# FPGA.net
KiCad netlist of a schematic drawn in Altium Designer
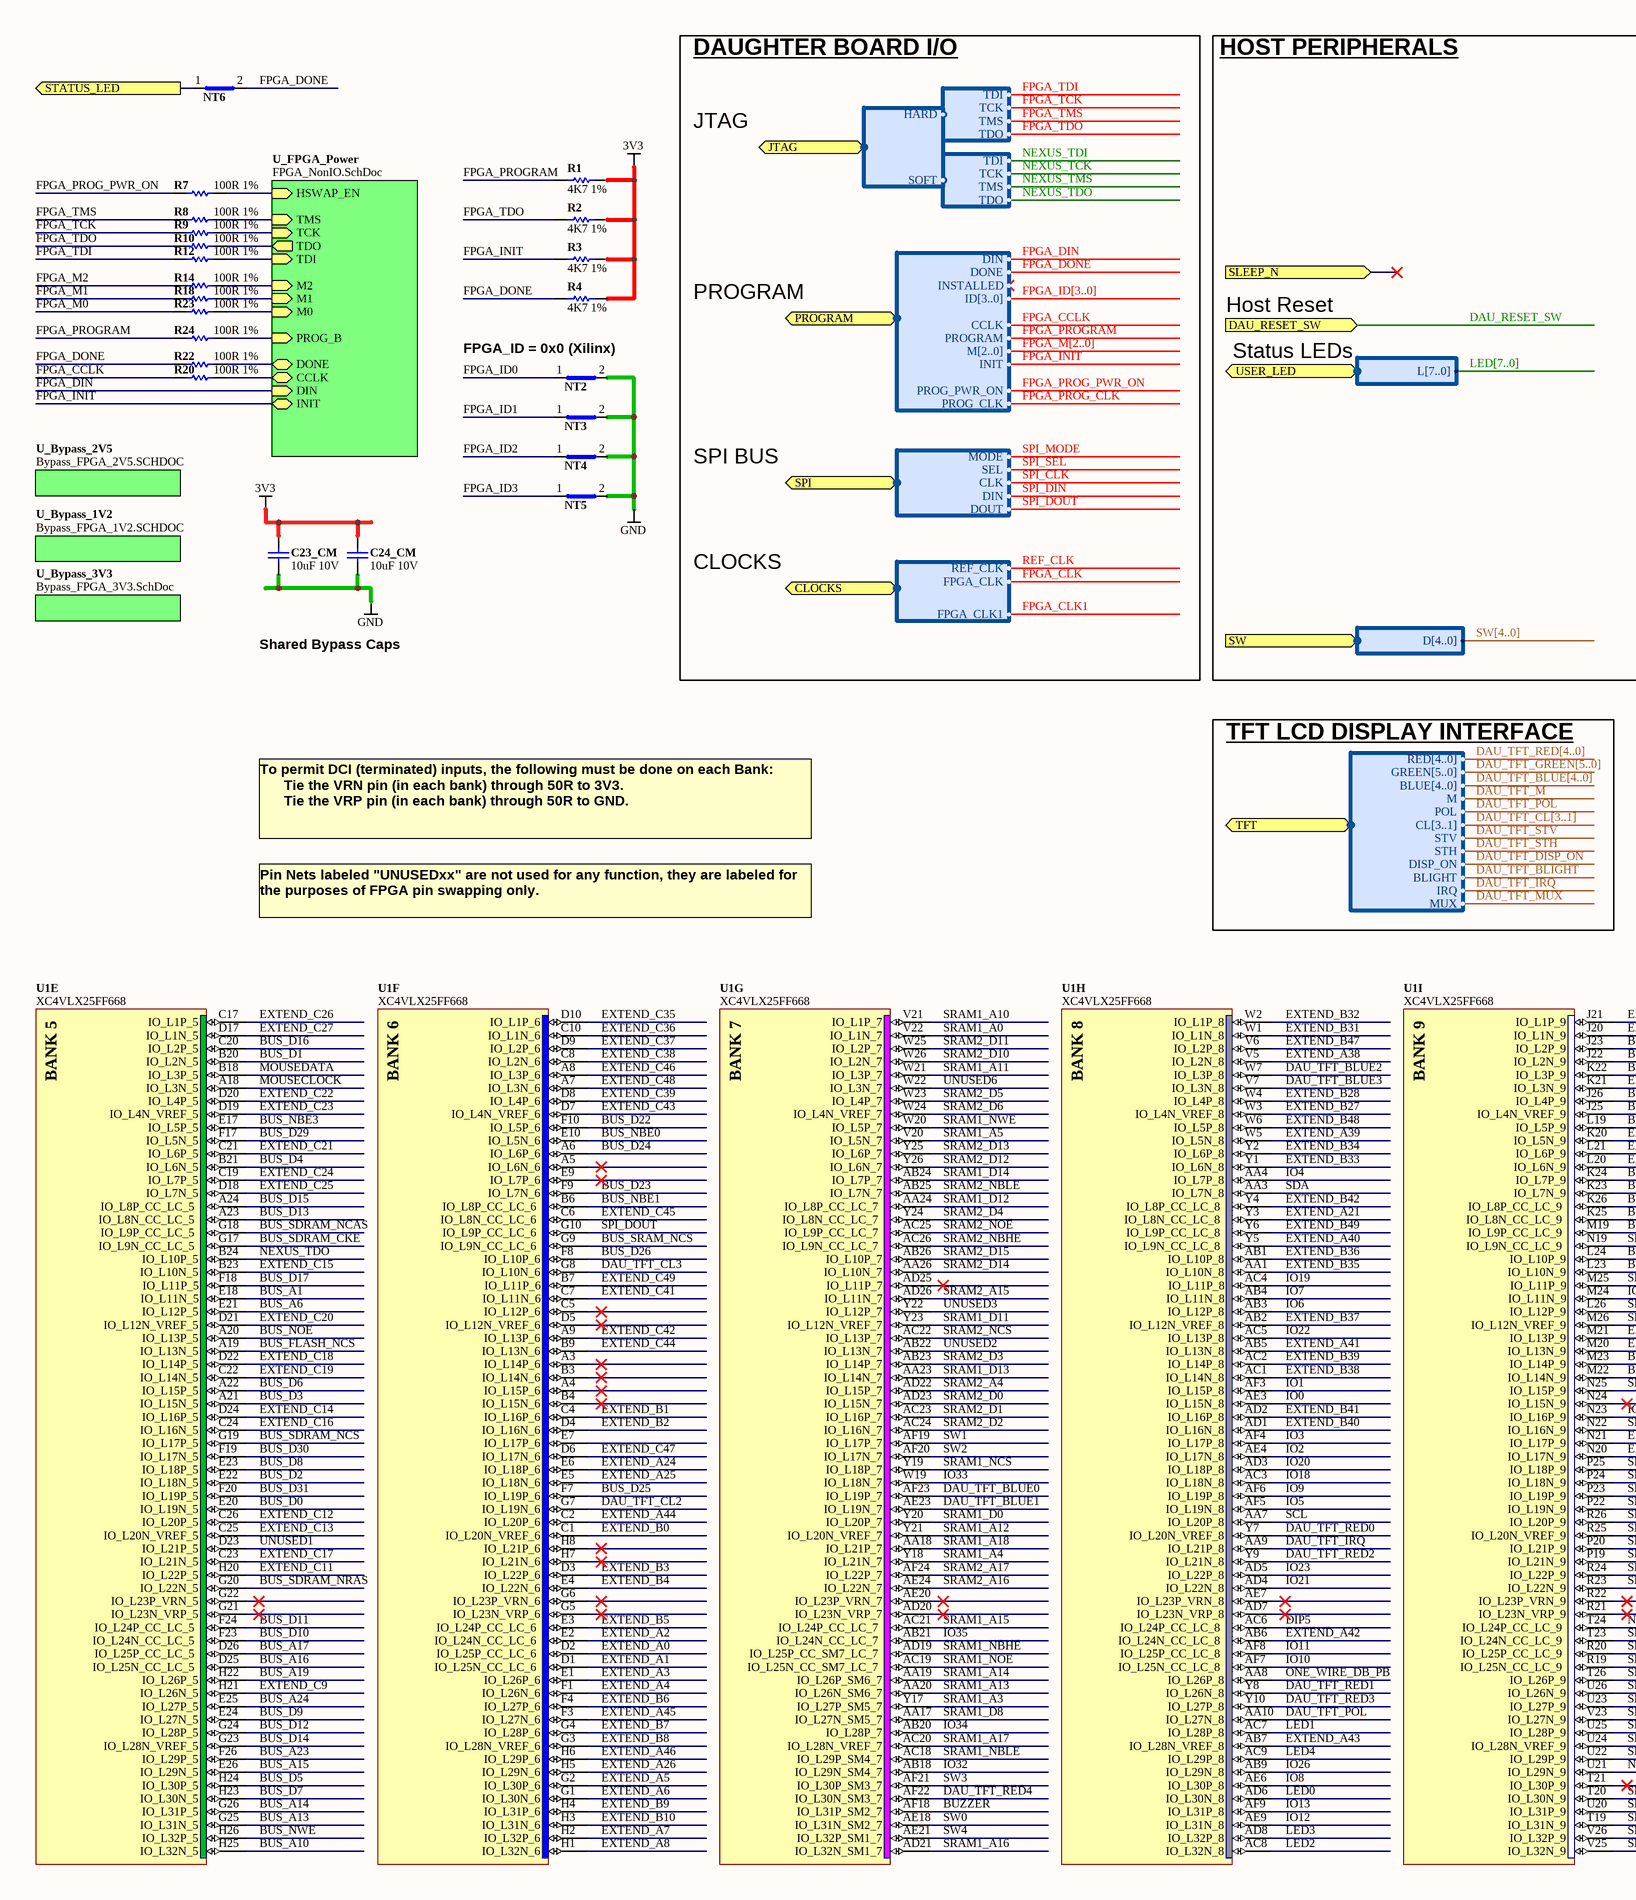
[diagram p0: FPGA.SCHDOC, left]
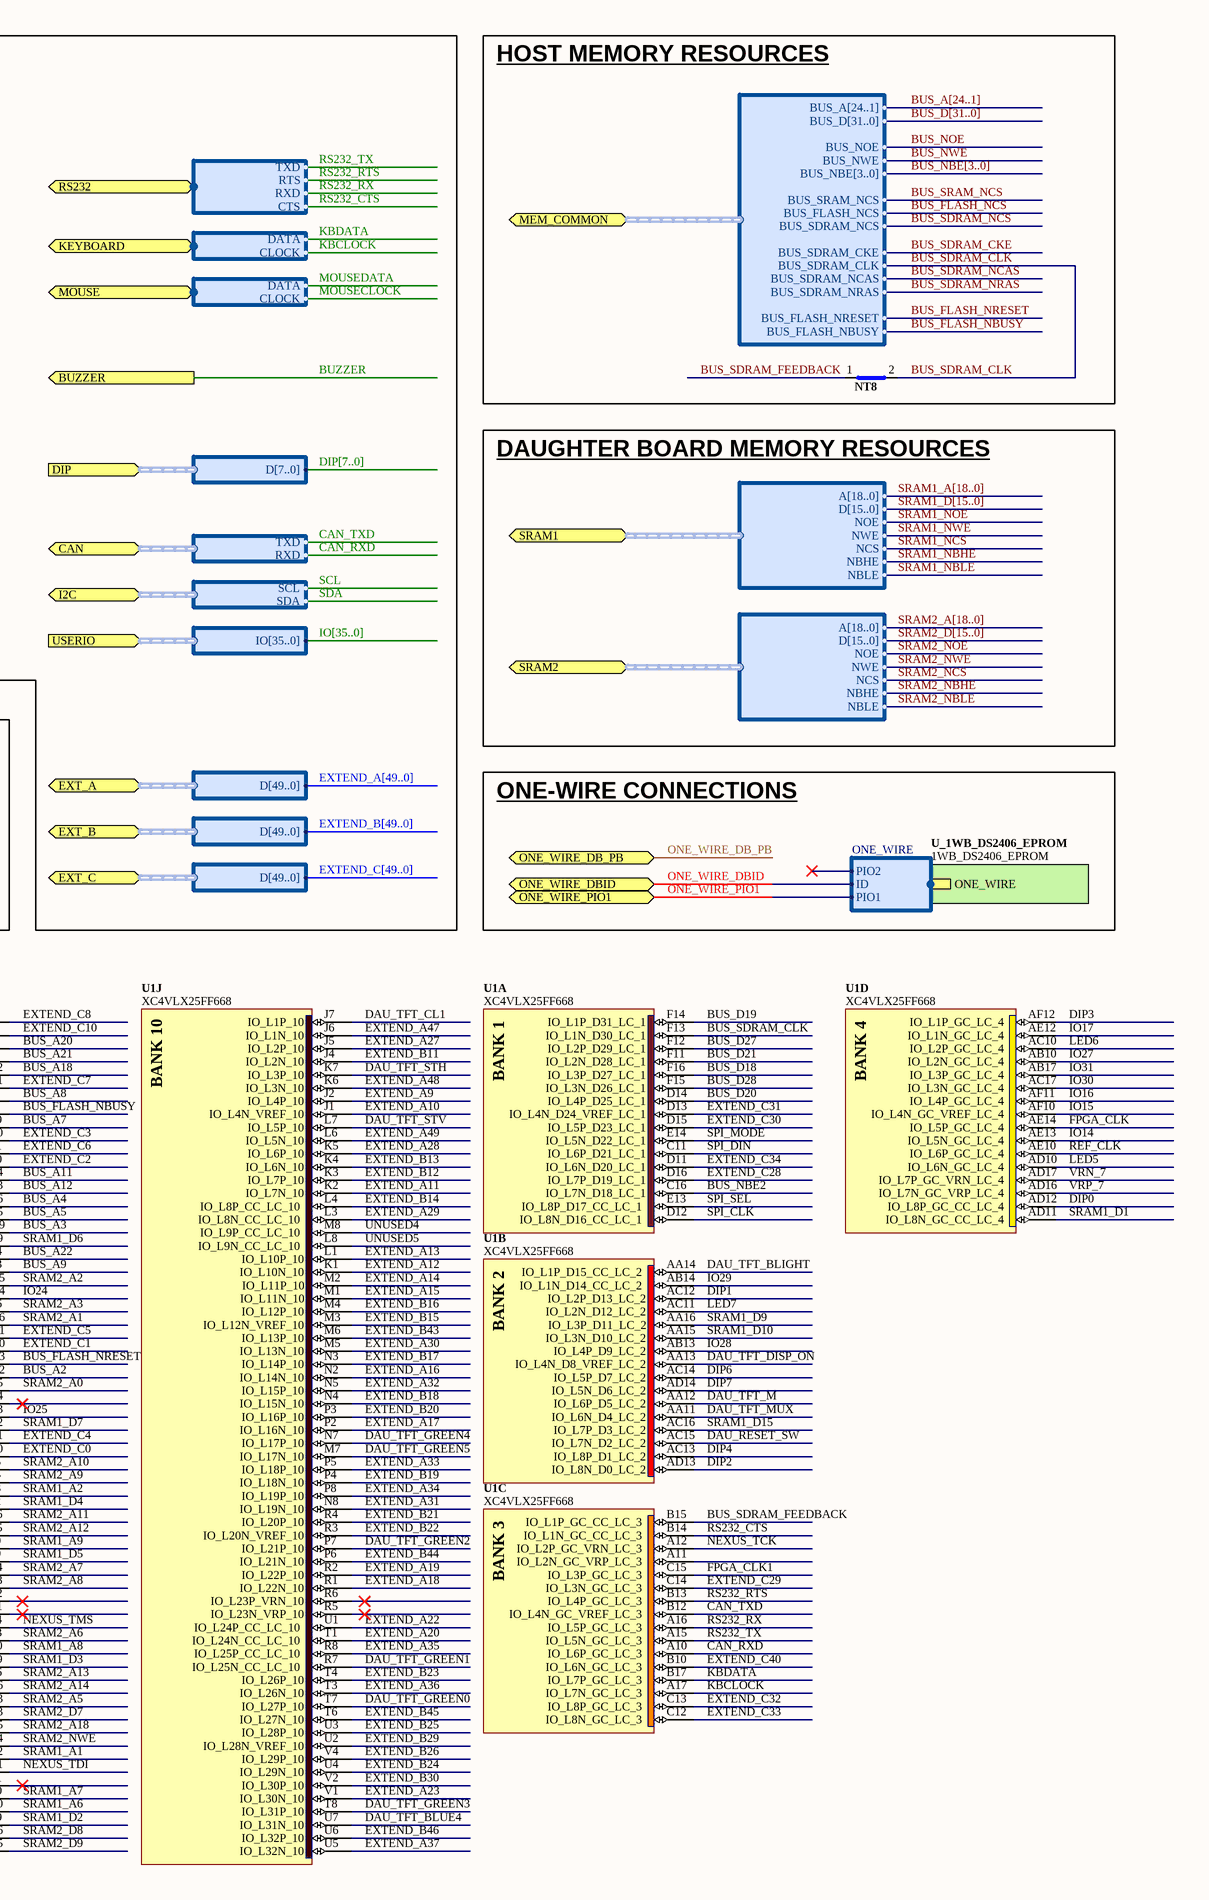
[diagram p1: FPGA.SCHDOC, right]

(export (version "E")
  (design (tool "Eeschema 10.0.6"))
  (components
    (comp (ref "C23_CM")
      (value "10uF 10V")
      (footprint "CAPC2012-STAR")
      (description "Capacitor, Ceramic, 10uF 10% 10V 0805 (2012) X5R")
      (fields (field (name "TOLERANCE") "10 %"))
      (libsource (lib "AltiumDesignLibrary") (part "CAP-NP"))
    )
    (comp (ref "C24_CM")
      (value "10uF 10V")
      (footprint "CAPC2012-STAR")
      (description "Capacitor, Ceramic, 10uF 10% 10V 0805 (2012) X5R")
      (fields (field (name "TOLERANCE") "10 %"))
      (libsource (lib "AltiumDesignLibrary") (part "CAP-NP"))
    )
    (comp (ref "NT2")
      (value "Net Tie SMT2")
      (footprint "NETTIE-SMT2-8X8")
      (description "Net-Tie, Surface Mount, 2 x 0.4mm x 0.2mm SMT Pads - For 0.2mm Track")
      (libsource (lib "AltiumDesignLibrary") (part "NETTIE-SMT2"))
    )
    (comp (ref "NT3")
      (value "Net Tie SMT2")
      (footprint "NETTIE-SMT2-8X8")
      (description "Net-Tie, Surface Mount, 2 x 0.4mm x 0.2mm SMT Pads - For 0.2mm Track")
      (libsource (lib "AltiumDesignLibrary") (part "NETTIE-SMT2"))
    )
    (comp (ref "NT4")
      (value "Net Tie SMT2")
      (footprint "NETTIE-SMT2-8X8")
      (description "Net-Tie, Surface Mount, 2 x 0.4mm x 0.2mm SMT Pads - For 0.2mm Track")
      (libsource (lib "AltiumDesignLibrary") (part "NETTIE-SMT2"))
    )
    (comp (ref "NT5")
      (value "Net Tie SMT2")
      (footprint "NETTIE-SMT2-8X8")
      (description "Net-Tie, Surface Mount, 2 x 0.4mm x 0.2mm SMT Pads - For 0.2mm Track")
      (libsource (lib "AltiumDesignLibrary") (part "NETTIE-SMT2"))
    )
    (comp (ref "NT6")
      (value "Net Tie SMT2")
      (footprint "NETTIE-SMT2-8X8")
      (description "Net-Tie, Surface Mount, 2 x 0.4mm x 0.2mm SMT Pads - For 0.2mm Track")
      (libsource (lib "AltiumDesignLibrary") (part "NETTIE-SMT2"))
    )
    (comp (ref "NT8")
      (value "Net Tie SMT2")
      (footprint "NETTIE-SMT2-8X8")
      (description "Net-Tie, Surface Mount, 2 x 0.4mm x 0.2mm SMT Pads - For 0.2mm Track")
      (libsource (lib "AltiumDesignLibrary") (part "NETTIE-SMT2"))
    )
    (comp (ref "R1")
      (value "4K7 1%")
      (footprint "RESC1005-STAR")
      (description "Resistor, 4K7 1% 0402 (1005)")
      (fields (field (name "TOLERANCE") "1 %"))
      (libsource (lib "AltiumDesignLibrary") (part "RES"))
    )
    (comp (ref "R2")
      (value "4K7 1%")
      (footprint "RESC1005-STAR")
      (description "Resistor, 4K7 1% 0402 (1005)")
      (fields (field (name "TOLERANCE") "1 %"))
      (libsource (lib "AltiumDesignLibrary") (part "RES"))
    )
    (comp (ref "R3")
      (value "4K7 1%")
      (footprint "RESC1005-STAR")
      (description "Resistor, 4K7 1% 0402 (1005)")
      (fields (field (name "TOLERANCE") "1 %"))
      (libsource (lib "AltiumDesignLibrary") (part "RES"))
    )
    (comp (ref "R4")
      (value "4K7 1%")
      (footprint "RESC1005-STAR")
      (description "Resistor, 4K7 1% 0402 (1005)")
      (fields (field (name "TOLERANCE") "1 %"))
      (libsource (lib "AltiumDesignLibrary") (part "RES"))
    )
    (comp (ref "R7")
      (value "100R 1%")
      (footprint "RESC1005-STAR")
      (description "Resistor, 100R 1% 0402 (1005)")
      (fields (field (name "TOLERANCE") "1 %"))
      (libsource (lib "AltiumDesignLibrary") (part "RES"))
    )
    (comp (ref "R8")
      (value "100R 1%")
      (footprint "RESC1005-STAR")
      (description "Resistor, 100R 1% 0402 (1005)")
      (fields (field (name "TOLERANCE") "1 %"))
      (libsource (lib "AltiumDesignLibrary") (part "RES"))
    )
    (comp (ref "R9")
      (value "100R 1%")
      (footprint "RESC1005-STAR")
      (description "Resistor, 100R 1% 0402 (1005)")
      (fields (field (name "TOLERANCE") "1 %"))
      (libsource (lib "AltiumDesignLibrary") (part "RES"))
    )
    (comp (ref "R10")
      (value "100R 1%")
      (footprint "RESC1005-STAR")
      (description "Resistor, 100R 1% 0402 (1005)")
      (fields (field (name "TOLERANCE") "1 %"))
      (libsource (lib "AltiumDesignLibrary") (part "RES"))
    )
    (comp (ref "R12")
      (value "100R 1%")
      (footprint "RESC1005-STAR")
      (description "Resistor, 100R 1% 0402 (1005)")
      (fields (field (name "TOLERANCE") "1 %"))
      (libsource (lib "AltiumDesignLibrary") (part "RES"))
    )
    (comp (ref "R14")
      (value "100R 1%")
      (footprint "RESC1005-STAR")
      (description "Resistor, 100R 1% 0402 (1005)")
      (fields (field (name "TOLERANCE") "1 %"))
      (libsource (lib "AltiumDesignLibrary") (part "RES"))
    )
    (comp (ref "R18")
      (value "100R 1%")
      (footprint "RESC1005-STAR")
      (description "Resistor, 100R 1% 0402 (1005)")
      (fields (field (name "TOLERANCE") "1 %"))
      (libsource (lib "AltiumDesignLibrary") (part "RES"))
    )
    (comp (ref "R20")
      (value "100R 1%")
      (footprint "RESC1005-STAR")
      (description "Resistor, 100R 1% 0402 (1005)")
      (fields (field (name "TOLERANCE") "1 %"))
      (libsource (lib "AltiumDesignLibrary") (part "RES"))
    )
    (comp (ref "R22")
      (value "100R 1%")
      (footprint "RESC1005-STAR")
      (description "Resistor, 100R 1% 0402 (1005)")
      (fields (field (name "TOLERANCE") "1 %"))
      (libsource (lib "AltiumDesignLibrary") (part "RES"))
    )
    (comp (ref "R23")
      (value "100R 1%")
      (footprint "RESC1005-STAR")
      (description "Resistor, 100R 1% 0402 (1005)")
      (fields (field (name "TOLERANCE") "1 %"))
      (libsource (lib "AltiumDesignLibrary") (part "RES"))
    )
    (comp (ref "R24")
      (value "100R 1%")
      (footprint "RESC1005-STAR")
      (description "Resistor, 100R 1% 0402 (1005)")
      (fields (field (name "TOLERANCE") "1 %"))
      (libsource (lib "AltiumDesignLibrary") (part "RES"))
    )
    (comp (ref "U1")
      (value "XC4VLX25FF668")
      (footprint "XC4VLX25-10FF668C")
      (description "FPGA, Xilinx Virtex-4, XC4VLX25")
      (libsource (lib "AltiumDesignLibrary") (part "XC4VLX25-10FF668C"))
    )
  )
  (nets
    (net (code "20") (name "/BUS_A1") (class "Default")
      (node (ref "U1") (pin "E18") (pinfunction "IO_L11N_5_E18") (pintype "bidirectional"))
    )
    (net (code "21") (name "/BUS_A2") (class "Default")
      (node (ref "U1") (pin "M22") (pinfunction "IO_L14N_9_M22") (pintype "bidirectional"))
    )
    (net (code "22") (name "/BUS_A3") (class "Default")
      (node (ref "U1") (pin "M19") (pinfunction "IO_L9P_CC_LC_9_M19") (pintype "bidirectional"))
    )
    (net (code "23") (name "/BUS_A4") (class "Default")
      (node (ref "U1") (pin "K26") (pinfunction "IO_L8P_CC_LC_9_K26") (pintype "bidirectional"))
    )
    (net (code "24") (name "/BUS_A5") (class "Default")
      (node (ref "U1") (pin "K25") (pinfunction "IO_L8N_CC_LC_9_K25") (pintype "bidirectional"))
    )
    (net (code "25") (name "/BUS_A6") (class "Default")
      (node (ref "U1") (pin "E21") (pinfunction "IO_L12P_5_E21") (pintype "bidirectional"))
    )
    (net (code "26") (name "/BUS_A7") (class "Default")
      (node (ref "U1") (pin "L19") (pinfunction "IO_L5P_9_L19") (pintype "bidirectional"))
    )
    (net (code "27") (name "/BUS_A8") (class "Default")
      (node (ref "U1") (pin "J26") (pinfunction "IO_L4P_9_J26") (pintype "bidirectional"))
    )
    (net (code "28") (name "/BUS_A9") (class "Default")
      (node (ref "U1") (pin "L23") (pinfunction "IO_L10N_9_L23") (pintype "bidirectional"))
    )
    (net (code "29") (name "/BUS_A10") (class "Default")
      (node (ref "U1") (pin "H25") (pinfunction "IO_L32N_5_H25") (pintype "bidirectional"))
    )
    (net (code "30") (name "/BUS_A11") (class "Default")
      (node (ref "U1") (pin "K24") (pinfunction "IO_L7P_9_K24") (pintype "bidirectional"))
    )
    (net (code "31") (name "/BUS_A12") (class "Default")
      (node (ref "U1") (pin "K23") (pinfunction "IO_L7N_9_K23") (pintype "bidirectional"))
    )
    (net (code "32") (name "/BUS_A13") (class "Default")
      (node (ref "U1") (pin "G25") (pinfunction "IO_L31N_5_G25") (pintype "bidirectional"))
    )
    (net (code "33") (name "/BUS_A14") (class "Default")
      (node (ref "U1") (pin "G26") (pinfunction "IO_L31P_5_G26") (pintype "bidirectional"))
    )
    (net (code "34") (name "/BUS_A15") (class "Default")
      (node (ref "U1") (pin "E26") (pinfunction "IO_L29N_5_E26") (pintype "bidirectional"))
    )
    (net (code "35") (name "/BUS_A16") (class "Default")
      (node (ref "U1") (pin "D25") (pinfunction "IO_L25N_CC_LC_5_D25") (pintype "bidirectional"))
    )
    (net (code "36") (name "/BUS_A17") (class "Default")
      (node (ref "U1") (pin "D26") (pinfunction "IO_L25P_CC_LC_5_D26") (pintype "bidirectional"))
    )
    (net (code "37") (name "/BUS_A18") (class "Default")
      (node (ref "U1") (pin "K22") (pinfunction "IO_L3P_9_K22") (pintype "bidirectional"))
    )
    (net (code "38") (name "/BUS_A19") (class "Default")
      (node (ref "U1") (pin "H22") (pinfunction "IO_L26P_5_H22") (pintype "bidirectional"))
    )
    (net (code "39") (name "/BUS_A20") (class "Default")
      (node (ref "U1") (pin "J23") (pinfunction "IO_L2P_9_J23") (pintype "bidirectional"))
    )
    (net (code "40") (name "/BUS_A21") (class "Default")
      (node (ref "U1") (pin "J22") (pinfunction "IO_L2N_9_J22") (pintype "bidirectional"))
    )
    (net (code "41") (name "/BUS_A22") (class "Default")
      (node (ref "U1") (pin "L24") (pinfunction "IO_L10P_9_L24") (pintype "bidirectional"))
    )
    (net (code "42") (name "/BUS_A23") (class "Default")
      (node (ref "U1") (pin "F26") (pinfunction "IO_L29P_5_F26") (pintype "bidirectional"))
    )
    (net (code "43") (name "/BUS_A24") (class "Default")
      (node (ref "U1") (pin "E25") (pinfunction "IO_L27P_5_E25") (pintype "bidirectional"))
    )
    (net (code "45") (name "/BUS_D0") (class "Default")
      (node (ref "U1") (pin "E20") (pinfunction "IO_L19N_5_E20") (pintype "bidirectional"))
    )
    (net (code "46") (name "/BUS_D1") (class "Default")
      (node (ref "U1") (pin "B20") (pinfunction "IO_L2N_5_B20") (pintype "bidirectional"))
    )
    (net (code "47") (name "/BUS_D2") (class "Default")
      (node (ref "U1") (pin "E22") (pinfunction "IO_L18N_5_E22") (pintype "bidirectional"))
    )
    (net (code "48") (name "/BUS_D3") (class "Default")
      (node (ref "U1") (pin "A21") (pinfunction "IO_L15N_5_A21") (pintype "bidirectional"))
    )
    (net (code "49") (name "/BUS_D4") (class "Default")
      (node (ref "U1") (pin "B21") (pinfunction "IO_L6N_5_B21") (pintype "bidirectional"))
    )
    (net (code "50") (name "/BUS_D5") (class "Default")
      (node (ref "U1") (pin "H24") (pinfunction "IO_L30P_5_H24") (pintype "bidirectional"))
    )
    (net (code "51") (name "/BUS_D6") (class "Default")
      (node (ref "U1") (pin "A22") (pinfunction "IO_L15P_5_A22") (pintype "bidirectional"))
    )
    (net (code "52") (name "/BUS_D7") (class "Default")
      (node (ref "U1") (pin "H23") (pinfunction "IO_L30N_5_H23") (pintype "bidirectional"))
    )
    (net (code "53") (name "/BUS_D8") (class "Default")
      (node (ref "U1") (pin "E23") (pinfunction "IO_L18P_5_E23") (pintype "bidirectional"))
    )
    (net (code "54") (name "/BUS_D9") (class "Default")
      (node (ref "U1") (pin "E24") (pinfunction "IO_L27N_5_E24") (pintype "bidirectional"))
    )
    (net (code "55") (name "/BUS_D10") (class "Default")
      (node (ref "U1") (pin "F23") (pinfunction "IO_L24N_CC_LC_5_F23") (pintype "bidirectional"))
    )
    (net (code "56") (name "/BUS_D11") (class "Default")
      (node (ref "U1") (pin "F24") (pinfunction "IO_L24P_CC_LC_5_F24") (pintype "bidirectional"))
    )
    (net (code "57") (name "/BUS_D12") (class "Default")
      (node (ref "U1") (pin "G24") (pinfunction "IO_L28P_5_G24") (pintype "bidirectional"))
    )
    (net (code "58") (name "/BUS_D13") (class "Default")
      (node (ref "U1") (pin "A23") (pinfunction "IO_L8N_CC_LC_5_A23") (pintype "bidirectional"))
    )
    (net (code "59") (name "/BUS_D14") (class "Default")
      (node (ref "U1") (pin "G23") (pinfunction "IO_L28N_VREF_5_G23") (pintype "bidirectional"))
    )
    (net (code "60") (name "/BUS_D15") (class "Default")
      (node (ref "U1") (pin "A24") (pinfunction "IO_L8P_CC_LC_5_A24") (pintype "bidirectional"))
    )
    (net (code "61") (name "/BUS_D16") (class "Default")
      (node (ref "U1") (pin "C20") (pinfunction "IO_L2P_5_C20") (pintype "bidirectional"))
    )
    (net (code "62") (name "/BUS_D17") (class "Default")
      (node (ref "U1") (pin "F18") (pinfunction "IO_L11P_5_F18") (pintype "bidirectional"))
    )
    (net (code "63") (name "/BUS_D18") (class "Default")
      (node (ref "U1") (pin "F16") (pinfunction "IO_L3P_D27_LC_1_F16") (pintype "bidirectional"))
    )
    (net (code "64") (name "/BUS_D19") (class "Default")
      (node (ref "U1") (pin "F14") (pinfunction "IO_L1P_D31_LC_1_F14") (pintype "bidirectional"))
    )
    (net (code "65") (name "/BUS_D20") (class "Default")
      (node (ref "U1") (pin "D14") (pinfunction "IO_L4P_D25_LC_1_D14") (pintype "bidirectional"))
    )
    (net (code "66") (name "/BUS_D21") (class "Default")
      (node (ref "U1") (pin "F11") (pinfunction "IO_L2N_D28_LC_1_F11") (pintype "bidirectional"))
    )
    (net (code "67") (name "/BUS_D22") (class "Default")
      (node (ref "U1") (pin "F10") (pinfunction "IO_L5P_6_F10") (pintype "bidirectional"))
    )
    (net (code "68") (name "/BUS_D23") (class "Default")
      (node (ref "U1") (pin "F9") (pinfunction "IO_L7N_6_F9") (pintype "bidirectional"))
    )
    (net (code "69") (name "/BUS_D24") (class "Default")
      (node (ref "U1") (pin "A6") (pinfunction "IO_L6P_6_A6") (pintype "bidirectional"))
    )
    (net (code "70") (name "/BUS_D25") (class "Default")
      (node (ref "U1") (pin "F7") (pinfunction "IO_L19P_6_F7") (pintype "bidirectional"))
    )
    (net (code "71") (name "/BUS_D26") (class "Default")
      (node (ref "U1") (pin "F8") (pinfunction "IO_L10P_6_F8") (pintype "bidirectional"))
    )
    (net (code "72") (name "/BUS_D27") (class "Default")
      (node (ref "U1") (pin "F12") (pinfunction "IO_L2P_D29_LC_1_F12") (pintype "bidirectional"))
    )
    (net (code "73") (name "/BUS_D28") (class "Default")
      (node (ref "U1") (pin "F15") (pinfunction "IO_L3N_D26_LC_1_F15") (pintype "bidirectional"))
    )
    (net (code "74") (name "/BUS_D29") (class "Default")
      (node (ref "U1") (pin "F17") (pinfunction "IO_L5N_5_F17") (pintype "bidirectional"))
    )
    (net (code "75") (name "/BUS_D30") (class "Default")
      (node (ref "U1") (pin "F19") (pinfunction "IO_L17N_5_F19") (pintype "bidirectional"))
    )
    (net (code "76") (name "/BUS_D31") (class "Default")
      (node (ref "U1") (pin "F20") (pinfunction "IO_L19P_5_F20") (pintype "bidirectional"))
    )
    (net (code "78") (name "/BUS_FLASH_NBUSY") (class "Default")
      (node (ref "U1") (pin "J25") (pinfunction "IO_L4N_VREF_9_J25") (pintype "bidirectional"))
    )
    (net (code "79") (name "/BUS_FLASH_NCS") (class "Default")
      (node (ref "U1") (pin "A19") (pinfunction "IO_L13N_5_A19") (pintype "bidirectional"))
    )
    (net (code "80") (name "/BUS_FLASH_NRESET") (class "Default")
      (node (ref "U1") (pin "M23") (pinfunction "IO_L14P_9_M23") (pintype "bidirectional"))
    )
    (net (code "81") (name "/BUS_NBE0") (class "Default")
      (node (ref "U1") (pin "E10") (pinfunction "IO_L5N_6_E10") (pintype "bidirectional"))
    )
    (net (code "82") (name "/BUS_NBE1") (class "Default")
      (node (ref "U1") (pin "B6") (pinfunction "IO_L8P_CC_LC_6_B6") (pintype "bidirectional"))
    )
    (net (code "83") (name "/BUS_NBE2") (class "Default")
      (node (ref "U1") (pin "C16") (pinfunction "IO_L7N_D18_LC_1_C16") (pintype "bidirectional"))
    )
    (net (code "84") (name "/BUS_NBE3") (class "Default")
      (node (ref "U1") (pin "E17") (pinfunction "IO_L5P_5_E17") (pintype "bidirectional"))
    )
    (net (code "86") (name "/BUS_NOE") (class "Default")
      (node (ref "U1") (pin "A20") (pinfunction "IO_L13P_5_A20") (pintype "bidirectional"))
    )
    (net (code "87") (name "/BUS_NWE") (class "Default")
      (node (ref "U1") (pin "H26") (pinfunction "IO_L32P_5_H26") (pintype "bidirectional"))
    )
    (net (code "88") (name "/BUS_SDRAM_CKE") (class "Default")
      (node (ref "U1") (pin "G17") (pinfunction "IO_L9N_CC_LC_5_G17") (pintype "bidirectional"))
    )
    (net (code "89") (name "/BUS_SDRAM_CLK") (class "Default")
      (node (ref "NT8") (pin "2") (pinfunction "Net2_2") (pintype "passive"))
      (node (ref "U1") (pin "F13") (pinfunction "IO_L1N_D30_LC_1_F13") (pintype "bidirectional"))
    )
    (net (code "90") (name "/BUS_SDRAM_FEEDBACK") (class "Default")
      (node (ref "NT8") (pin "1") (pinfunction "Net1_1") (pintype "passive"))
      (node (ref "U1") (pin "B15") (pinfunction "IO_L1P_GC_CC_LC_3_B15") (pintype "bidirectional"))
    )
    (net (code "91") (name "/BUS_SDRAM_NCAS") (class "Default")
      (node (ref "U1") (pin "G18") (pinfunction "IO_L9P_CC_LC_5_G18") (pintype "bidirectional"))
    )
    (net (code "92") (name "/BUS_SDRAM_NCS") (class "Default")
      (node (ref "U1") (pin "G19") (pinfunction "IO_L17P_5_G19") (pintype "bidirectional"))
    )
    (net (code "93") (name "/BUS_SDRAM_NRAS") (class "Default")
      (node (ref "U1") (pin "G20") (pinfunction "IO_L22N_5_G20") (pintype "bidirectional"))
    )
    (net (code "94") (name "/BUS_SRAM_NCS") (class "Default")
      (node (ref "U1") (pin "G9") (pinfunction "IO_L9N_CC_LC_6_G9") (pintype "bidirectional"))
    )
    (net (code "95") (name "/BUZZER") (class "Default")
      (node (ref "U1") (pin "AF18") (pinfunction "IO_L31P_SM2_7_AF18") (pintype "bidirectional"))
    )
    (net (code "96") (name "/CAN_RXD") (class "Default")
      (node (ref "U1") (pin "A10") (pinfunction "IO_L6P_GC_LC_3_A10") (pintype "bidirectional"))
    )
    (net (code "97") (name "/CAN_TXD") (class "Default")
      (node (ref "U1") (pin "B12") (pinfunction "IO_L4N_GC_VREF_LC_3_B12") (pintype "bidirectional"))
    )
    (net (code "98") (name "/CCLK") (class "Default")
      (node (ref "R20") (pin "2") (pinfunction "2_2") (pintype "passive"))
    )
    (net (code "99") (name "/DAU_RESET_SW") (class "Default")
      (node (ref "U1") (pin "AC15") (pinfunction "IO_L7N_D2_LC_2_AC15") (pintype "bidirectional"))
    )
    (net (code "100") (name "/DAU_TFT_BLIGHT") (class "Default")
      (node (ref "U1") (pin "AA14") (pinfunction "IO_L1P_D15_CC_LC_2_AA14") (pintype "bidirectional"))
    )
    (net (code "101") (name "/DAU_TFT_BLUE0") (class "Default")
      (node (ref "U1") (pin "AF23") (pinfunction "IO_L19P_7_AF23") (pintype "bidirectional"))
    )
    (net (code "102") (name "/DAU_TFT_BLUE1") (class "Default")
      (node (ref "U1") (pin "AE23") (pinfunction "IO_L19N_7_AE23") (pintype "bidirectional"))
    )
    (net (code "103") (name "/DAU_TFT_BLUE2") (class "Default")
      (node (ref "U1") (pin "W7") (pinfunction "IO_L3P_8_W7") (pintype "bidirectional"))
    )
    (net (code "104") (name "/DAU_TFT_BLUE3") (class "Default")
      (node (ref "U1") (pin "V7") (pinfunction "IO_L3N_8_V7") (pintype "bidirectional"))
    )
    (net (code "105") (name "/DAU_TFT_BLUE4") (class "Default")
      (node (ref "U1") (pin "U7") (pinfunction "IO_L31N_10_U7") (pintype "bidirectional"))
    )
    (net (code "107") (name "/DAU_TFT_CL1") (class "Default")
      (node (ref "U1") (pin "J7") (pinfunction "IO_L1P_10_J7") (pintype "bidirectional"))
    )
    (net (code "108") (name "/DAU_TFT_CL2") (class "Default")
      (node (ref "U1") (pin "G7") (pinfunction "IO_L19N_6_G7") (pintype "bidirectional"))
    )
    (net (code "109") (name "/DAU_TFT_CL3") (class "Default")
      (node (ref "U1") (pin "G8") (pinfunction "IO_L10N_6_G8") (pintype "bidirectional"))
    )
    (net (code "110") (name "/DAU_TFT_DISP_ON") (class "Default")
      (node (ref "U1") (pin "AA13") (pinfunction "IO_L4N_D8_VREF_LC_2_AA13") (pintype "bidirectional"))
    )
    (net (code "111") (name "/DAU_TFT_GREEN0") (class "Default")
      (node (ref "U1") (pin "T7") (pinfunction "IO_L27P_10_T7") (pintype "bidirectional"))
    )
    (net (code "112") (name "/DAU_TFT_GREEN1") (class "Default")
      (node (ref "U1") (pin "R7") (pinfunction "IO_L25N_CC_LC_10_R7") (pintype "bidirectional"))
    )
    (net (code "113") (name "/DAU_TFT_GREEN2") (class "Default")
      (node (ref "U1") (pin "P7") (pinfunction "IO_L21P_10_P7") (pintype "bidirectional"))
    )
    (net (code "114") (name "/DAU_TFT_GREEN3") (class "Default")
      (node (ref "U1") (pin "T8") (pinfunction "IO_L31P_10_T8") (pintype "bidirectional"))
    )
    (net (code "115") (name "/DAU_TFT_GREEN4") (class "Default")
      (node (ref "U1") (pin "N7") (pinfunction "IO_L17P_10_N7") (pintype "bidirectional"))
    )
    (net (code "116") (name "/DAU_TFT_GREEN5") (class "Default")
      (node (ref "U1") (pin "M7") (pinfunction "IO_L17N_10_M7") (pintype "bidirectional"))
    )
    (net (code "118") (name "/DAU_TFT_IRQ") (class "Default")
      (node (ref "U1") (pin "AA9") (pinfunction "IO_L21P_8_AA9") (pintype "bidirectional"))
    )
    (net (code "119") (name "/DAU_TFT_M") (class "Default")
      (node (ref "U1") (pin "AA12") (pinfunction "IO_L6P_D5_LC_2_AA12") (pintype "bidirectional"))
    )
    (net (code "120") (name "/DAU_TFT_MUX") (class "Default")
      (node (ref "U1") (pin "AA11") (pinfunction "IO_L6N_D4_LC_2_AA11") (pintype "bidirectional"))
    )
    (net (code "121") (name "/DAU_TFT_POL") (class "Default")
      (node (ref "U1") (pin "AA10") (pinfunction "IO_L27N_8_AA10") (pintype "bidirectional"))
    )
    (net (code "122") (name "/DAU_TFT_RED0") (class "Default")
      (node (ref "U1") (pin "Y7") (pinfunction "IO_L20N_VREF_8_Y7") (pintype "bidirectional"))
    )
    (net (code "123") (name "/DAU_TFT_RED1") (class "Default")
      (node (ref "U1") (pin "Y8") (pinfunction "IO_L26N_8_Y8") (pintype "bidirectional"))
    )
    (net (code "124") (name "/DAU_TFT_RED2") (class "Default")
      (node (ref "U1") (pin "Y9") (pinfunction "IO_L21N_8_Y9") (pintype "bidirectional"))
    )
    (net (code "125") (name "/DAU_TFT_RED3") (class "Default")
      (node (ref "U1") (pin "Y10") (pinfunction "IO_L27P_8_Y10") (pintype "bidirectional"))
    )
    (net (code "126") (name "/DAU_TFT_RED4") (class "Default")
      (node (ref "U1") (pin "AF22") (pinfunction "IO_L30N_SM3_7_AF22") (pintype "bidirectional"))
    )
    (net (code "128") (name "/DAU_TFT_STH") (class "Default")
      (node (ref "U1") (pin "K7") (pinfunction "IO_L3P_10_K7") (pintype "bidirectional"))
    )
    (net (code "129") (name "/DAU_TFT_STV") (class "Default")
      (node (ref "U1") (pin "L7") (pinfunction "IO_L5P_10_L7") (pintype "bidirectional"))
    )
    (net (code "130") (name "/DIP0") (class "Default")
      (node (ref "U1") (pin "AD12") (pinfunction "IO_L8P_GC_CC_LC_4_AD12") (pintype "bidirectional"))
    )
    (net (code "131") (name "/DIP1") (class "Default")
      (node (ref "U1") (pin "AC12") (pinfunction "IO_L2P_D13_LC_2_AC12") (pintype "bidirectional"))
    )
    (net (code "132") (name "/DIP2") (class "Default")
      (node (ref "U1") (pin "AD13") (pinfunction "IO_L8N_D0_LC_2_AD13") (pintype "bidirectional"))
    )
    (net (code "133") (name "/DIP3") (class "Default")
      (node (ref "U1") (pin "AF12") (pinfunction "IO_L1P_GC_LC_4_AF12") (pintype "bidirectional"))
    )
    (net (code "134") (name "/DIP4") (class "Default")
      (node (ref "U1") (pin "AC13") (pinfunction "IO_L8P_D1_LC_2_AC13") (pintype "bidirectional"))
    )
    (net (code "135") (name "/DIP5") (class "Default")
      (node (ref "U1") (pin "AC6") (pinfunction "IO_L24P_CC_LC_8_AC6") (pintype "bidirectional"))
    )
    (net (code "136") (name "/DIP6") (class "Default")
      (node (ref "U1") (pin "AC14") (pinfunction "IO_L5P_D7_LC_2_AC14") (pintype "bidirectional"))
    )
    (net (code "137") (name "/DIP7") (class "Default")
      (node (ref "U1") (pin "AD14") (pinfunction "IO_L5N_D6_LC_2_AD14") (pintype "bidirectional"))
    )
    (net (code "139") (name "/DONE") (class "Default")
      (node (ref "R22") (pin "2") (pinfunction "2_2") (pintype "passive"))
    )
    (net (code "140") (name "/EXTEND_A0") (class "Default")
      (node (ref "U1") (pin "D2") (pinfunction "IO_L25P_CC_LC_6_D2") (pintype "bidirectional"))
    )
    (net (code "141") (name "/EXTEND_A1") (class "Default")
      (node (ref "U1") (pin "D1") (pinfunction "IO_L25N_CC_LC_6_D1") (pintype "bidirectional"))
    )
    (net (code "142") (name "/EXTEND_A2") (class "Default")
      (node (ref "U1") (pin "E2") (pinfunction "IO_L24N_CC_LC_6_E2") (pintype "bidirectional"))
    )
    (net (code "143") (name "/EXTEND_A3") (class "Default")
      (node (ref "U1") (pin "E1") (pinfunction "IO_L26P_6_E1") (pintype "bidirectional"))
    )
    (net (code "144") (name "/EXTEND_A4") (class "Default")
      (node (ref "U1") (pin "F1") (pinfunction "IO_L26N_6_F1") (pintype "bidirectional"))
    )
    (net (code "145") (name "/EXTEND_A5") (class "Default")
      (node (ref "U1") (pin "G2") (pinfunction "IO_L30P_6_G2") (pintype "bidirectional"))
    )
    (net (code "146") (name "/EXTEND_A6") (class "Default")
      (node (ref "U1") (pin "G1") (pinfunction "IO_L30N_6_G1") (pintype "bidirectional"))
    )
    (net (code "147") (name "/EXTEND_A7") (class "Default")
      (node (ref "U1") (pin "H2") (pinfunction "IO_L32P_6_H2") (pintype "bidirectional"))
    )
    (net (code "148") (name "/EXTEND_A8") (class "Default")
      (node (ref "U1") (pin "H1") (pinfunction "IO_L32N_6_H1") (pintype "bidirectional"))
    )
    (net (code "149") (name "/EXTEND_A9") (class "Default")
      (node (ref "U1") (pin "J2") (pinfunction "IO_L4P_10_J2") (pintype "bidirectional"))
    )
    (net (code "150") (name "/EXTEND_A10") (class "Default")
      (node (ref "U1") (pin "J1") (pinfunction "IO_L4N_VREF_10_J1") (pintype "bidirectional"))
    )
    (net (code "151") (name "/EXTEND_A11") (class "Default")
      (node (ref "U1") (pin "K2") (pinfunction "IO_L7N_10_K2") (pintype "bidirectional"))
    )
    (net (code "152") (name "/EXTEND_A12") (class "Default")
      (node (ref "U1") (pin "K1") (pinfunction "IO_L10N_10_K1") (pintype "bidirectional"))
    )
    (net (code "153") (name "/EXTEND_A13") (class "Default")
      (node (ref "U1") (pin "L1") (pinfunction "IO_L10P_10_L1") (pintype "bidirectional"))
    )
    (net (code "154") (name "/EXTEND_A14") (class "Default")
      (node (ref "U1") (pin "M2") (pinfunction "IO_L11P_10_M2") (pintype "bidirectional"))
    )
    (net (code "155") (name "/EXTEND_A15") (class "Default")
      (node (ref "U1") (pin "M1") (pinfunction "IO_L11N_10_M1") (pintype "bidirectional"))
    )
    (net (code "156") (name "/EXTEND_A16") (class "Default")
      (node (ref "U1") (pin "N2") (pinfunction "IO_L14N_10_N2") (pintype "bidirectional"))
    )
    (net (code "157") (name "/EXTEND_A17") (class "Default")
      (node (ref "U1") (pin "P2") (pinfunction "IO_L16N_10_P2") (pintype "bidirectional"))
    )
    (net (code "158") (name "/EXTEND_A18") (class "Default")
      (node (ref "U1") (pin "R1") (pinfunction "IO_L22N_10_R1") (pintype "bidirectional"))
    )
    (net (code "159") (name "/EXTEND_A19") (class "Default")
      (node (ref "U1") (pin "R2") (pinfunction "IO_L22P_10_R2") (pintype "bidirectional"))
    )
    (net (code "160") (name "/EXTEND_A20") (class "Default")
      (node (ref "U1") (pin "T1") (pinfunction "IO_L24N_CC_LC_10_T1") (pintype "bidirectional"))
    )
    (net (code "161") (name "/EXTEND_A21") (class "Default")
      (node (ref "U1") (pin "Y3") (pinfunction "IO_L8N_CC_LC_8_Y3") (pintype "bidirectional"))
    )
    (net (code "162") (name "/EXTEND_A22") (class "Default")
      (node (ref "U1") (pin "U1") (pinfunction "IO_L24P_CC_LC_10_U1") (pintype "bidirectional"))
    )
    (net (code "163") (name "/EXTEND_A23") (class "Default")
      (node (ref "U1") (pin "V1") (pinfunction "IO_L30N_10_V1") (pintype "bidirectional"))
    )
    (net (code "164") (name "/EXTEND_A24") (class "Default")
      (node (ref "U1") (pin "E6") (pinfunction "IO_L18P_6_E6") (pintype "bidirectional"))
    )
    (net (code "165") (name "/EXTEND_A25") (class "Default")
      (node (ref "U1") (pin "E5") (pinfunction "IO_L18N_6_E5") (pintype "bidirectional"))
    )
    (net (code "166") (name "/EXTEND_A26") (class "Default")
      (node (ref "U1") (pin "H5") (pinfunction "IO_L29N_6_H5") (pintype "bidirectional"))
    )
    (net (code "167") (name "/EXTEND_A27") (class "Default")
      (node (ref "U1") (pin "J5") (pinfunction "IO_L2P_10_J5") (pintype "bidirectional"))
    )
    (net (code "168") (name "/EXTEND_A28") (class "Default")
      (node (ref "U1") (pin "K5") (pinfunction "IO_L6P_10_K5") (pintype "bidirectional"))
    )
    (net (code "169") (name "/EXTEND_A29") (class "Default")
      (node (ref "U1") (pin "L3") (pinfunction "IO_L8N_CC_LC_10_L3") (pintype "bidirectional"))
    )
    (net (code "170") (name "/EXTEND_A30") (class "Default")
      (node (ref "U1") (pin "M5") (pinfunction "IO_L13N_10_M5") (pintype "bidirectional"))
    )
    (net (code "171") (name "/EXTEND_A31") (class "Default")
      (node (ref "U1") (pin "N8") (pinfunction "IO_L19N_10_N8") (pintype "bidirectional"))
    )
    (net (code "172") (name "/EXTEND_A32") (class "Default")
      (node (ref "U1") (pin "N5") (pinfunction "IO_L15P_10_N5") (pintype "bidirectional"))
    )
    (net (code "173") (name "/EXTEND_A33") (class "Default")
      (node (ref "U1") (pin "P5") (pinfunction "IO_L18P_10_P5") (pintype "bidirectional"))
    )
    (net (code "174") (name "/EXTEND_A34") (class "Default")
      (node (ref "U1") (pin "P8") (pinfunction "IO_L19P_10_P8") (pintype "bidirectional"))
    )
    (net (code "175") (name "/EXTEND_A35") (class "Default")
      (node (ref "U1") (pin "R8") (pinfunction "IO_L25P_CC_LC_10_R8") (pintype "bidirectional"))
    )
    (net (code "176") (name "/EXTEND_A36") (class "Default")
      (node (ref "U1") (pin "T3") (pinfunction "IO_L26N_10_T3") (pintype "bidirectional"))
    )
    (net (code "177") (name "/EXTEND_A37") (class "Default")
      (node (ref "U1") (pin "U5") (pinfunction "IO_L32N_10_U5") (pintype "bidirectional"))
    )
    (net (code "178") (name "/EXTEND_A38") (class "Default")
      (node (ref "U1") (pin "V5") (pinfunction "IO_L2N_8_V5") (pintype "bidirectional"))
    )
    (net (code "179") (name "/EXTEND_A39") (class "Default")
      (node (ref "U1") (pin "W5") (pinfunction "IO_L5N_8_W5") (pintype "bidirectional"))
    )
    (net (code "180") (name "/EXTEND_A40") (class "Default")
      (node (ref "U1") (pin "Y5") (pinfunction "IO_L9N_CC_LC_8_Y5") (pintype "bidirectional"))
    )
    (net (code "181") (name "/EXTEND_A41") (class "Default")
      (node (ref "U1") (pin "AB5") (pinfunction "IO_L13N_8_AB5") (pintype "bidirectional"))
    )
    (net (code "182") (name "/EXTEND_A42") (class "Default")
      (node (ref "U1") (pin "AB6") (pinfunction "IO_L24N_CC_LC_8_AB6") (pintype "bidirectional"))
    )
    (net (code "183") (name "/EXTEND_A43") (class "Default")
      (node (ref "U1") (pin "AB7") (pinfunction "IO_L28N_VREF_8_AB7") (pintype "bidirectional"))
    )
    (net (code "184") (name "/EXTEND_A44") (class "Default")
      (node (ref "U1") (pin "C2") (pinfunction "IO_L20P_6_C2") (pintype "bidirectional"))
    )
    (net (code "185") (name "/EXTEND_A45") (class "Default")
      (node (ref "U1") (pin "F3") (pinfunction "IO_L27N_6_F3") (pintype "bidirectional"))
    )
    (net (code "186") (name "/EXTEND_A46") (class "Default")
      (node (ref "U1") (pin "H6") (pinfunction "IO_L29P_6_H6") (pintype "bidirectional"))
    )
    (net (code "187") (name "/EXTEND_A47") (class "Default")
      (node (ref "U1") (pin "J6") (pinfunction "IO_L1N_10_J6") (pintype "bidirectional"))
    )
    (net (code "188") (name "/EXTEND_A48") (class "Default")
      (node (ref "U1") (pin "K6") (pinfunction "IO_L3N_10_K6") (pintype "bidirectional"))
    )
    (net (code "189") (name "/EXTEND_A49") (class "Default")
      (node (ref "U1") (pin "L6") (pinfunction "IO_L5N_10_L6") (pintype "bidirectional"))
    )
    (net (code "190") (name "/EXTEND_B0") (class "Default")
      (node (ref "U1") (pin "C1") (pinfunction "IO_L20N_VREF_6_C1") (pintype "bidirectional"))
    )
    (net (code "191") (name "/EXTEND_B1") (class "Default")
      (node (ref "U1") (pin "C4") (pinfunction "IO_L16P_6_C4") (pintype "bidirectional"))
    )
    (net (code "192") (name "/EXTEND_B2") (class "Default")
      (node (ref "U1") (pin "D4") (pinfunction "IO_L16N_6_D4") (pintype "bidirectional"))
    )
    (net (code "193") (name "/EXTEND_B3") (class "Default")
      (node (ref "U1") (pin "D3") (pinfunction "IO_L22P_6_D3") (pintype "bidirectional"))
    )
    (net (code "194") (name "/EXTEND_B4") (class "Default")
      (node (ref "U1") (pin "E4") (pinfunction "IO_L22N_6_E4") (pintype "bidirectional"))
    )
    (net (code "195") (name "/EXTEND_B5") (class "Default")
      (node (ref "U1") (pin "E3") (pinfunction "IO_L24P_CC_LC_6_E3") (pintype "bidirectional"))
    )
    (net (code "196") (name "/EXTEND_B6") (class "Default")
      (node (ref "U1") (pin "F4") (pinfunction "IO_L27P_6_F4") (pintype "bidirectional"))
    )
    (net (code "197") (name "/EXTEND_B7") (class "Default")
      (node (ref "U1") (pin "G4") (pinfunction "IO_L28P_6_G4") (pintype "bidirectional"))
    )
    (net (code "198") (name "/EXTEND_B8") (class "Default")
      (node (ref "U1") (pin "G3") (pinfunction "IO_L28N_VREF_6_G3") (pintype "bidirectional"))
    )
    (net (code "199") (name "/EXTEND_B9") (class "Default")
      (node (ref "U1") (pin "H4") (pinfunction "IO_L31P_6_H4") (pintype "bidirectional"))
    )
    (net (code "200") (name "/EXTEND_B10") (class "Default")
      (node (ref "U1") (pin "H3") (pinfunction "IO_L31N_6_H3") (pintype "bidirectional"))
    )
    (net (code "201") (name "/EXTEND_B11") (class "Default")
      (node (ref "U1") (pin "J4") (pinfunction "IO_L2N_10_J4") (pintype "bidirectional"))
    )
    (net (code "202") (name "/EXTEND_B12") (class "Default")
      (node (ref "U1") (pin "K3") (pinfunction "IO_L7P_10_K3") (pintype "bidirectional"))
    )
    (net (code "203") (name "/EXTEND_B13") (class "Default")
      (node (ref "U1") (pin "K4") (pinfunction "IO_L6N_10_K4") (pintype "bidirectional"))
    )
    (net (code "204") (name "/EXTEND_B14") (class "Default")
      (node (ref "U1") (pin "L4") (pinfunction "IO_L8P_CC_LC_10_L4") (pintype "bidirectional"))
    )
    (net (code "205") (name "/EXTEND_B15") (class "Default")
      (node (ref "U1") (pin "M3") (pinfunction "IO_L12N_VREF_10_M3") (pintype "bidirectional"))
    )
    (net (code "206") (name "/EXTEND_B16") (class "Default")
      (node (ref "U1") (pin "M4") (pinfunction "IO_L12P_10_M4") (pintype "bidirectional"))
    )
    (net (code "207") (name "/EXTEND_B17") (class "Default")
      (node (ref "U1") (pin "N3") (pinfunction "IO_L14P_10_N3") (pintype "bidirectional"))
    )
    (net (code "208") (name "/EXTEND_B18") (class "Default")
      (node (ref "U1") (pin "N4") (pinfunction "IO_L15N_10_N4") (pintype "bidirectional"))
    )
    (net (code "209") (name "/EXTEND_B19") (class "Default")
      (node (ref "U1") (pin "P4") (pinfunction "IO_L18N_10_P4") (pintype "bidirectional"))
    )
    (net (code "210") (name "/EXTEND_B20") (class "Default")
      (node (ref "U1") (pin "P3") (pinfunction "IO_L16P_10_P3") (pintype "bidirectional"))
    )
    (net (code "211") (name "/EXTEND_B21") (class "Default")
      (node (ref "U1") (pin "R4") (pinfunction "IO_L20P_10_R4") (pintype "bidirectional"))
    )
    (net (code "212") (name "/EXTEND_B22") (class "Default")
      (node (ref "U1") (pin "R3") (pinfunction "IO_L20N_VREF_10_R3") (pintype "bidirectional"))
    )
    (net (code "213") (name "/EXTEND_B23") (class "Default")
      (node (ref "U1") (pin "T4") (pinfunction "IO_L26P_10_T4") (pintype "bidirectional"))
    )
    (net (code "214") (name "/EXTEND_B24") (class "Default")
      (node (ref "U1") (pin "U4") (pinfunction "IO_L29N_10_U4") (pintype "bidirectional"))
    )
    (net (code "215") (name "/EXTEND_B25") (class "Default")
      (node (ref "U1") (pin "U3") (pinfunction "IO_L28P_10_U3") (pintype "bidirectional"))
    )
    (net (code "216") (name "/EXTEND_B26") (class "Default")
      (node (ref "U1") (pin "V4") (pinfunction "IO_L29P_10_V4") (pintype "bidirectional"))
    )
    (net (code "217") (name "/EXTEND_B27") (class "Default")
      (node (ref "U1") (pin "W3") (pinfunction "IO_L4N_VREF_8_W3") (pintype "bidirectional"))
    )
    (net (code "218") (name "/EXTEND_B28") (class "Default")
      (node (ref "U1") (pin "W4") (pinfunction "IO_L4P_8_W4") (pintype "bidirectional"))
    )
    (net (code "219") (name "/EXTEND_B29") (class "Default")
      (node (ref "U1") (pin "U2") (pinfunction "IO_L28N_VREF_10_U2") (pintype "bidirectional"))
    )
    (net (code "220") (name "/EXTEND_B30") (class "Default")
      (node (ref "U1") (pin "V2") (pinfunction "IO_L30P_10_V2") (pintype "bidirectional"))
    )
    (net (code "221") (name "/EXTEND_B31") (class "Default")
      (node (ref "U1") (pin "W1") (pinfunction "IO_L1N_8_W1") (pintype "bidirectional"))
    )
    (net (code "222") (name "/EXTEND_B32") (class "Default")
      (node (ref "U1") (pin "W2") (pinfunction "IO_L1P_8_W2") (pintype "bidirectional"))
    )
    (net (code "223") (name "/EXTEND_B33") (class "Default")
      (node (ref "U1") (pin "Y1") (pinfunction "IO_L6N_8_Y1") (pintype "bidirectional"))
    )
    (net (code "224") (name "/EXTEND_B34") (class "Default")
      (node (ref "U1") (pin "Y2") (pinfunction "IO_L6P_8_Y2") (pintype "bidirectional"))
    )
    (net (code "225") (name "/EXTEND_B35") (class "Default")
      (node (ref "U1") (pin "AA1") (pinfunction "IO_L10N_8_AA1") (pintype "bidirectional"))
    )
    (net (code "226") (name "/EXTEND_B36") (class "Default")
      (node (ref "U1") (pin "AB1") (pinfunction "IO_L10P_8_AB1") (pintype "bidirectional"))
    )
    (net (code "227") (name "/EXTEND_B37") (class "Default")
      (node (ref "U1") (pin "AB2") (pinfunction "IO_L12N_VREF_8_AB2") (pintype "bidirectional"))
    )
    (net (code "228") (name "/EXTEND_B38") (class "Default")
      (node (ref "U1") (pin "AC1") (pinfunction "IO_L14N_8_AC1") (pintype "bidirectional"))
    )
    (net (code "229") (name "/EXTEND_B39") (class "Default")
      (node (ref "U1") (pin "AC2") (pinfunction "IO_L14P_8_AC2") (pintype "bidirectional"))
    )
    (net (code "230") (name "/EXTEND_B40") (class "Default")
      (node (ref "U1") (pin "AD1") (pinfunction "IO_L16N_8_AD1") (pintype "bidirectional"))
    )
    (net (code "231") (name "/EXTEND_B41") (class "Default")
      (node (ref "U1") (pin "AD2") (pinfunction "IO_L16P_8_AD2") (pintype "bidirectional"))
    )
    (net (code "232") (name "/EXTEND_B42") (class "Default")
      (node (ref "U1") (pin "Y4") (pinfunction "IO_L8P_CC_LC_8_Y4") (pintype "bidirectional"))
    )
    (net (code "233") (name "/EXTEND_B43") (class "Default")
      (node (ref "U1") (pin "M6") (pinfunction "IO_L13P_10_M6") (pintype "bidirectional"))
    )
    (net (code "234") (name "/EXTEND_B44") (class "Default")
      (node (ref "U1") (pin "P6") (pinfunction "IO_L21N_10_P6") (pintype "bidirectional"))
    )
    (net (code "235") (name "/EXTEND_B45") (class "Default")
      (node (ref "U1") (pin "T6") (pinfunction "IO_L27N_10_T6") (pintype "bidirectional"))
    )
    (net (code "236") (name "/EXTEND_B46") (class "Default")
      (node (ref "U1") (pin "U6") (pinfunction "IO_L32P_10_U6") (pintype "bidirectional"))
    )
    (net (code "237") (name "/EXTEND_B47") (class "Default")
      (node (ref "U1") (pin "V6") (pinfunction "IO_L2P_8_V6") (pintype "bidirectional"))
    )
    (net (code "238") (name "/EXTEND_B48") (class "Default")
      (node (ref "U1") (pin "W6") (pinfunction "IO_L5P_8_W6") (pintype "bidirectional"))
    )
    (net (code "239") (name "/EXTEND_B49") (class "Default")
      (node (ref "U1") (pin "Y6") (pinfunction "IO_L9P_CC_LC_8_Y6") (pintype "bidirectional"))
    )
    (net (code "240") (name "/EXTEND_C0") (class "Default")
      (node (ref "U1") (pin "N20") (pinfunction "IO_L17N_9_N20") (pintype "bidirectional"))
    )
    (net (code "241") (name "/EXTEND_C1") (class "Default")
      (node (ref "U1") (pin "M20") (pinfunction "IO_L13N_9_M20") (pintype "bidirectional"))
    )
    (net (code "242") (name "/EXTEND_C2") (class "Default")
      (node (ref "U1") (pin "L20") (pinfunction "IO_L6N_9_L20") (pintype "bidirectional"))
    )
    (net (code "243") (name "/EXTEND_C3") (class "Default")
      (node (ref "U1") (pin "K20") (pinfunction "IO_L5N_9_K20") (pintype "bidirectional"))
    )
    (net (code "244") (name "/EXTEND_C4") (class "Default")
      (node (ref "U1") (pin "N21") (pinfunction "IO_L17P_9_N21") (pintype "bidirectional"))
    )
    (net (code "245") (name "/EXTEND_C5") (class "Default")
      (node (ref "U1") (pin "M21") (pinfunction "IO_L13P_9_M21") (pintype "bidirectional"))
    )
    (net (code "246") (name "/EXTEND_C6") (class "Default")
      (node (ref "U1") (pin "L21") (pinfunction "IO_L6P_9_L21") (pintype "bidirectional"))
    )
    (net (code "247") (name "/EXTEND_C7") (class "Default")
      (node (ref "U1") (pin "K21") (pinfunction "IO_L3N_9_K21") (pintype "bidirectional"))
    )
    (net (code "248") (name "/EXTEND_C8") (class "Default")
      (node (ref "U1") (pin "J21") (pinfunction "IO_L1P_9_J21") (pintype "bidirectional"))
    )
    (net (code "249") (name "/EXTEND_C9") (class "Default")
      (node (ref "U1") (pin "H21") (pinfunction "IO_L26N_5_H21") (pintype "bidirectional"))
    )
    (net (code "250") (name "/EXTEND_C10") (class "Default")
      (node (ref "U1") (pin "J20") (pinfunction "IO_L1N_9_J20") (pintype "bidirectional"))
    )
    (net (code "251") (name "/EXTEND_C11") (class "Default")
      (node (ref "U1") (pin "H20") (pinfunction "IO_L22P_5_H20") (pintype "bidirectional"))
    )
    (net (code "252") (name "/EXTEND_C12") (class "Default")
      (node (ref "U1") (pin "C26") (pinfunction "IO_L20P_5_C26") (pintype "bidirectional"))
    )
    (net (code "253") (name "/EXTEND_C13") (class "Default")
      (node (ref "U1") (pin "C25") (pinfunction "IO_L20N_VREF_5_C25") (pintype "bidirectional"))
    )
    (net (code "254") (name "/EXTEND_C14") (class "Default")
      (node (ref "U1") (pin "D24") (pinfunction "IO_L16P_5_D24") (pintype "bidirectional"))
    )
    (net (code "255") (name "/EXTEND_C15") (class "Default")
      (node (ref "U1") (pin "B23") (pinfunction "IO_L10N_5_B23") (pintype "bidirectional"))
    )
    (net (code "256") (name "/EXTEND_C16") (class "Default")
      (node (ref "U1") (pin "C24") (pinfunction "IO_L16N_5_C24") (pintype "bidirectional"))
    )
    (net (code "257") (name "/EXTEND_C17") (class "Default")
      (node (ref "U1") (pin "C23") (pinfunction "IO_L21N_5_C23") (pintype "bidirectional"))
    )
    (net (code "258") (name "/EXTEND_C18") (class "Default")
      (node (ref "U1") (pin "D22") (pinfunction "IO_L14P_5_D22") (pintype "bidirectional"))
    )
    (net (code "259") (name "/EXTEND_C19") (class "Default")
      (node (ref "U1") (pin "C22") (pinfunction "IO_L14N_5_C22") (pintype "bidirectional"))
    )
    (net (code "260") (name "/EXTEND_C20") (class "Default")
      (node (ref "U1") (pin "D21") (pinfunction "IO_L12N_VREF_5_D21") (pintype "bidirectional"))
    )
    (net (code "261") (name "/EXTEND_C21") (class "Default")
      (node (ref "U1") (pin "C21") (pinfunction "IO_L6P_5_C21") (pintype "bidirectional"))
    )
    (net (code "262") (name "/EXTEND_C22") (class "Default")
      (node (ref "U1") (pin "D20") (pinfunction "IO_L4P_5_D20") (pintype "bidirectional"))
    )
    (net (code "263") (name "/EXTEND_C23") (class "Default")
      (node (ref "U1") (pin "D19") (pinfunction "IO_L4N_VREF_5_D19") (pintype "bidirectional"))
    )
    (net (code "264") (name "/EXTEND_C24") (class "Default")
      (node (ref "U1") (pin "C19") (pinfunction "IO_L7P_5_C19") (pintype "bidirectional"))
    )
    (net (code "265") (name "/EXTEND_C25") (class "Default")
      (node (ref "U1") (pin "D18") (pinfunction "IO_L7N_5_D18") (pintype "bidirectional"))
    )
    (net (code "266") (name "/EXTEND_C26") (class "Default")
      (node (ref "U1") (pin "C17") (pinfunction "IO_L1P_5_C17") (pintype "bidirectional"))
    )
    (net (code "267") (name "/EXTEND_C27") (class "Default")
      (node (ref "U1") (pin "D17") (pinfunction "IO_L1N_5_D17") (pintype "bidirectional"))
    )
    (net (code "268") (name "/EXTEND_C28") (class "Default")
      (node (ref "U1") (pin "D16") (pinfunction "IO_L7P_D19_LC_1_D16") (pintype "bidirectional"))
    )
    (net (code "269") (name "/EXTEND_C29") (class "Default")
      (node (ref "U1") (pin "C14") (pinfunction "IO_L3N_GC_LC_3_C14") (pintype "bidirectional"))
    )
    (net (code "270") (name "/EXTEND_C30") (class "Default")
      (node (ref "U1") (pin "D15") (pinfunction "IO_L5P_D23_LC_1_D15") (pintype "bidirectional"))
    )
    (net (code "271") (name "/EXTEND_C31") (class "Default")
      (node (ref "U1") (pin "D13") (pinfunction "IO_L4N_D24_VREF_LC_1_D13") (pintype "bidirectional"))
    )
    (net (code "272") (name "/EXTEND_C32") (class "Default")
      (node (ref "U1") (pin "C13") (pinfunction "IO_L8P_GC_LC_3_C13") (pintype "bidirectional"))
    )
    (net (code "273") (name "/EXTEND_C33") (class "Default")
      (node (ref "U1") (pin "C12") (pinfunction "IO_L8N_GC_LC_3_C12") (pintype "bidirectional"))
    )
    (net (code "274") (name "/EXTEND_C34") (class "Default")
      (node (ref "U1") (pin "D11") (pinfunction "IO_L6N_D20_LC_1_D11") (pintype "bidirectional"))
    )
    (net (code "275") (name "/EXTEND_C35") (class "Default")
      (node (ref "U1") (pin "D10") (pinfunction "IO_L1P_6_D10") (pintype "bidirectional"))
    )
    (net (code "276") (name "/EXTEND_C36") (class "Default")
      (node (ref "U1") (pin "C10") (pinfunction "IO_L1N_6_C10") (pintype "bidirectional"))
    )
    (net (code "277") (name "/EXTEND_C37") (class "Default")
      (node (ref "U1") (pin "D9") (pinfunction "IO_L2P_6_D9") (pintype "bidirectional"))
    )
    (net (code "278") (name "/EXTEND_C38") (class "Default")
      (node (ref "U1") (pin "C8") (pinfunction "IO_L2N_6_C8") (pintype "bidirectional"))
    )
    (net (code "279") (name "/EXTEND_C39") (class "Default")
      (node (ref "U1") (pin "D8") (pinfunction "IO_L4P_6_D8") (pintype "bidirectional"))
    )
    (net (code "280") (name "/EXTEND_C40") (class "Default")
      (node (ref "U1") (pin "B10") (pinfunction "IO_L6N_GC_LC_3_B10") (pintype "bidirectional"))
    )
    (net (code "281") (name "/EXTEND_C41") (class "Default")
      (node (ref "U1") (pin "C7") (pinfunction "IO_L11N_6_C7") (pintype "bidirectional"))
    )
    (net (code "282") (name "/EXTEND_C42") (class "Default")
      (node (ref "U1") (pin "A9") (pinfunction "IO_L13P_6_A9") (pintype "bidirectional"))
    )
    (net (code "283") (name "/EXTEND_C43") (class "Default")
      (node (ref "U1") (pin "D7") (pinfunction "IO_L4N_VREF_6_D7") (pintype "bidirectional"))
    )
    (net (code "284") (name "/EXTEND_C44") (class "Default")
      (node (ref "U1") (pin "B9") (pinfunction "IO_L13N_6_B9") (pintype "bidirectional"))
    )
    (net (code "285") (name "/EXTEND_C45") (class "Default")
      (node (ref "U1") (pin "C6") (pinfunction "IO_L8N_CC_LC_6_C6") (pintype "bidirectional"))
    )
    (net (code "286") (name "/EXTEND_C46") (class "Default")
      (node (ref "U1") (pin "A8") (pinfunction "IO_L3P_6_A8") (pintype "bidirectional"))
    )
    (net (code "287") (name "/EXTEND_C47") (class "Default")
      (node (ref "U1") (pin "D6") (pinfunction "IO_L17N_6_D6") (pintype "bidirectional"))
    )
    (net (code "288") (name "/EXTEND_C48") (class "Default")
      (node (ref "U1") (pin "A7") (pinfunction "IO_L3N_6_A7") (pintype "bidirectional"))
    )
    (net (code "289") (name "/EXTEND_C49") (class "Default")
      (node (ref "U1") (pin "B7") (pinfunction "IO_L11P_6_B7") (pintype "bidirectional"))
    )
    (net (code "293") (name "/FPGA_CCLK") (class "Default")
      (node (ref "R20") (pin "1") (pinfunction "1_1") (pintype "passive"))
    )
    (net (code "294") (name "/FPGA_CLK") (class "Default")
      (node (ref "U1") (pin "AE14") (pinfunction "IO_L5P_GC_LC_4_AE14") (pintype "bidirectional"))
    )
    (net (code "295") (name "/FPGA_CLK1") (class "Default")
      (node (ref "U1") (pin "C15") (pinfunction "IO_L3P_GC_LC_3_C15") (pintype "bidirectional"))
    )
    (net (code "297") (name "/FPGA_DONE") (class "Default")
      (node (ref "NT6") (pin "2") (pinfunction "Net2_2") (pintype "passive"))
      (node (ref "R22") (pin "1") (pinfunction "1_1") (pintype "passive"))
      (node (ref "R4") (pin "1") (pinfunction "1_1") (pintype "passive"))
    )
    (net (code "298") (name "/FPGA_ID0") (class "Default")
      (node (ref "NT2") (pin "1") (pinfunction "Net1_1") (pintype "passive"))
    )
    (net (code "299") (name "/FPGA_ID1") (class "Default")
      (node (ref "NT3") (pin "1") (pinfunction "Net1_1") (pintype "passive"))
    )
    (net (code "300") (name "/FPGA_ID2") (class "Default")
      (node (ref "NT4") (pin "1") (pinfunction "Net1_1") (pintype "passive"))
    )
    (net (code "301") (name "/FPGA_ID3") (class "Default")
      (node (ref "NT5") (pin "1") (pinfunction "Net1_1") (pintype "passive"))
    )
    (net (code "303") (name "/FPGA_INIT") (class "Default")
      (node (ref "R3") (pin "1") (pinfunction "1_1") (pintype "passive"))
    )
    (net (code "304") (name "/FPGA_M0") (class "Default")
      (node (ref "R23") (pin "1") (pinfunction "1_1") (pintype "passive"))
    )
    (net (code "305") (name "/FPGA_M1") (class "Default")
      (node (ref "R18") (pin "1") (pinfunction "1_1") (pintype "passive"))
    )
    (net (code "306") (name "/FPGA_M2") (class "Default")
      (node (ref "R14") (pin "1") (pinfunction "1_1") (pintype "passive"))
    )
    (net (code "307") (name "/FPGA_PROGRAM") (class "Default")
      (node (ref "R1") (pin "1") (pinfunction "1_1") (pintype "passive"))
      (node (ref "R24") (pin "1") (pinfunction "1_1") (pintype "passive"))
    )
    (net (code "309") (name "/FPGA_PROG_PWR_ON") (class "Default")
      (node (ref "R7") (pin "1") (pinfunction "1_1") (pintype "passive"))
    )
    (net (code "310") (name "/FPGA_TCK") (class "Default")
      (node (ref "R9") (pin "1") (pinfunction "1_1") (pintype "passive"))
    )
    (net (code "311") (name "/FPGA_TDI") (class "Default")
      (node (ref "R12") (pin "1") (pinfunction "1_1") (pintype "passive"))
    )
    (net (code "312") (name "/FPGA_TDO") (class "Default")
      (node (ref "R10") (pin "1") (pinfunction "1_1") (pintype "passive"))
      (node (ref "R2") (pin "1") (pinfunction "1_1") (pintype "passive"))
    )
    (net (code "313") (name "/FPGA_TMS") (class "Default")
      (node (ref "R8") (pin "1") (pinfunction "1_1") (pintype "passive"))
    )
    (net (code "314") (name "/HSWAP_EN") (class "Default")
      (node (ref "R7") (pin "2") (pinfunction "2_2") (pintype "passive"))
    )
    (net (code "315") (name "/IO0") (class "Default")
      (node (ref "U1") (pin "AE3") (pinfunction "IO_L15N_8_AE3") (pintype "bidirectional"))
    )
    (net (code "316") (name "/IO1") (class "Default")
      (node (ref "U1") (pin "AF3") (pinfunction "IO_L15P_8_AF3") (pintype "bidirectional"))
    )
    (net (code "317") (name "/IO2") (class "Default")
      (node (ref "U1") (pin "AE4") (pinfunction "IO_L17N_8_AE4") (pintype "bidirectional"))
    )
    (net (code "318") (name "/IO3") (class "Default")
      (node (ref "U1") (pin "AF4") (pinfunction "IO_L17P_8_AF4") (pintype "bidirectional"))
    )
    (net (code "319") (name "/IO4") (class "Default")
      (node (ref "U1") (pin "AA4") (pinfunction "IO_L7P_8_AA4") (pintype "bidirectional"))
    )
    (net (code "320") (name "/IO5") (class "Default")
      (node (ref "U1") (pin "AF5") (pinfunction "IO_L19N_8_AF5") (pintype "bidirectional"))
    )
    (net (code "321") (name "/IO6") (class "Default")
      (node (ref "U1") (pin "AB3") (pinfunction "IO_L12P_8_AB3") (pintype "bidirectional"))
    )
    (net (code "322") (name "/IO7") (class "Default")
      (node (ref "U1") (pin "AB4") (pinfunction "IO_L11N_8_AB4") (pintype "bidirectional"))
    )
    (net (code "323") (name "/IO8") (class "Default")
      (node (ref "U1") (pin "AE6") (pinfunction "IO_L30P_8_AE6") (pintype "bidirectional"))
    )
    (net (code "324") (name "/IO9") (class "Default")
      (node (ref "U1") (pin "AF6") (pinfunction "IO_L19P_8_AF6") (pintype "bidirectional"))
    )
    (net (code "325") (name "/IO10") (class "Default")
      (node (ref "U1") (pin "AF7") (pinfunction "IO_L25N_CC_LC_8_AF7") (pintype "bidirectional"))
    )
    (net (code "326") (name "/IO11") (class "Default")
      (node (ref "U1") (pin "AF8") (pinfunction "IO_L25P_CC_LC_8_AF8") (pintype "bidirectional"))
    )
    (net (code "327") (name "/IO12") (class "Default")
      (node (ref "U1") (pin "AE9") (pinfunction "IO_L31N_8_AE9") (pintype "bidirectional"))
    )
    (net (code "328") (name "/IO13") (class "Default")
      (node (ref "U1") (pin "AF9") (pinfunction "IO_L31P_8_AF9") (pintype "bidirectional"))
    )
    (net (code "329") (name "/IO14") (class "Default")
      (node (ref "U1") (pin "AE13") (pinfunction "IO_L5N_GC_LC_4_AE13") (pintype "bidirectional"))
    )
    (net (code "330") (name "/IO15") (class "Default")
      (node (ref "U1") (pin "AF10") (pinfunction "IO_L4N_GC_VREF_LC_4_AF10") (pintype "bidirectional"))
    )
    (net (code "331") (name "/IO16") (class "Default")
      (node (ref "U1") (pin "AF11") (pinfunction "IO_L4P_GC_LC_4_AF11") (pintype "bidirectional"))
    )
    (net (code "332") (name "/IO17") (class "Default")
      (node (ref "U1") (pin "AE12") (pinfunction "IO_L1N_GC_LC_4_AE12") (pintype "bidirectional"))
    )
    (net (code "333") (name "/IO18") (class "Default")
      (node (ref "U1") (pin "AC3") (pinfunction "IO_L18N_8_AC3") (pintype "bidirectional"))
    )
    (net (code "334") (name "/IO19") (class "Default")
      (node (ref "U1") (pin "AC4") (pinfunction "IO_L11P_8_AC4") (pintype "bidirectional"))
    )
    (net (code "335") (name "/IO20") (class "Default")
      (node (ref "U1") (pin "AD3") (pinfunction "IO_L18P_8_AD3") (pintype "bidirectional"))
    )
    (net (code "336") (name "/IO21") (class "Default")
      (node (ref "U1") (pin "AD4") (pinfunction "IO_L22N_8_AD4") (pintype "bidirectional"))
    )
    (net (code "337") (name "/IO22") (class "Default")
      (node (ref "U1") (pin "AC5") (pinfunction "IO_L13P_8_AC5") (pintype "bidirectional"))
    )
    (net (code "338") (name "/IO23") (class "Default")
      (node (ref "U1") (pin "AD5") (pinfunction "IO_L22P_8_AD5") (pintype "bidirectional"))
    )
    (net (code "339") (name "/IO24") (class "Default")
      (node (ref "U1") (pin "M24") (pinfunction "IO_L11N_9_M24") (pintype "bidirectional"))
    )
    (net (code "340") (name "/IO25") (class "Default")
      (node (ref "U1") (pin "N23") (pinfunction "IO_L16P_9_N23") (pintype "bidirectional"))
    )
    (net (code "341") (name "/IO26") (class "Default")
      (node (ref "U1") (pin "AB9") (pinfunction "IO_L29N_8_AB9") (pintype "bidirectional"))
    )
    (net (code "342") (name "/IO27") (class "Default")
      (node (ref "U1") (pin "AB10") (pinfunction "IO_L2N_GC_LC_4_AB10") (pintype "bidirectional"))
    )
    (net (code "343") (name "/IO28") (class "Default")
      (node (ref "U1") (pin "AB13") (pinfunction "IO_L4P_D9_LC_2_AB13") (pintype "bidirectional"))
    )
    (net (code "344") (name "/IO29") (class "Default")
      (node (ref "U1") (pin "AB14") (pinfunction "IO_L1N_D14_CC_LC_2_AB14") (pintype "bidirectional"))
    )
    (net (code "345") (name "/IO30") (class "Default")
      (node (ref "U1") (pin "AC17") (pinfunction "IO_L3N_GC_LC_4_AC17") (pintype "bidirectional"))
    )
    (net (code "346") (name "/IO31") (class "Default")
      (node (ref "U1") (pin "AB17") (pinfunction "IO_L3P_GC_LC_4_AB17") (pintype "bidirectional"))
    )
    (net (code "347") (name "/IO32") (class "Default")
      (node (ref "U1") (pin "AB18") (pinfunction "IO_L29N_SM4_7_AB18") (pintype "bidirectional"))
    )
    (net (code "348") (name "/IO33") (class "Default")
      (node (ref "U1") (pin "W19") (pinfunction "IO_L18N_7_W19") (pintype "bidirectional"))
    )
    (net (code "349") (name "/IO34") (class "Default")
      (node (ref "U1") (pin "AB20") (pinfunction "IO_L28P_7_AB20") (pintype "bidirectional"))
    )
    (net (code "350") (name "/IO35") (class "Default")
      (node (ref "U1") (pin "AB21") (pinfunction "IO_L24N_CC_LC_7_AB21") (pintype "bidirectional"))
    )
    (net (code "351") (name "/KBCLOCK") (class "Default")
      (node (ref "U1") (pin "A17") (pinfunction "IO_L7N_GC_LC_3_A17") (pintype "bidirectional"))
    )
    (net (code "352") (name "/KBDATA") (class "Default")
      (node (ref "U1") (pin "B17") (pinfunction "IO_L7P_GC_LC_3_B17") (pintype "bidirectional"))
    )
    (net (code "353") (name "/LED0") (class "Default")
      (node (ref "U1") (pin "AD6") (pinfunction "IO_L30N_8_AD6") (pintype "bidirectional"))
    )
    (net (code "354") (name "/LED1") (class "Default")
      (node (ref "U1") (pin "AC7") (pinfunction "IO_L28P_8_AC7") (pintype "bidirectional"))
    )
    (net (code "355") (name "/LED2") (class "Default")
      (node (ref "U1") (pin "AC8") (pinfunction "IO_L32N_8_AC8") (pintype "bidirectional"))
    )
    (net (code "356") (name "/LED3") (class "Default")
      (node (ref "U1") (pin "AD8") (pinfunction "IO_L32P_8_AD8") (pintype "bidirectional"))
    )
    (net (code "357") (name "/LED4") (class "Default")
      (node (ref "U1") (pin "AC9") (pinfunction "IO_L29P_8_AC9") (pintype "bidirectional"))
    )
    (net (code "358") (name "/LED5") (class "Default")
      (node (ref "U1") (pin "AD10") (pinfunction "IO_L6N_GC_LC_4_AD10") (pintype "bidirectional"))
    )
    (net (code "359") (name "/LED6") (class "Default")
      (node (ref "U1") (pin "AC10") (pinfunction "IO_L2P_GC_LC_4_AC10") (pintype "bidirectional"))
    )
    (net (code "360") (name "/LED7") (class "Default")
      (node (ref "U1") (pin "AC11") (pinfunction "IO_L2N_D12_LC_2_AC11") (pintype "bidirectional"))
    )
    (net (code "361") (name "/M0") (class "Default")
      (node (ref "R23") (pin "2") (pinfunction "2_2") (pintype "passive"))
    )
    (net (code "362") (name "/M1") (class "Default")
      (node (ref "R18") (pin "2") (pinfunction "2_2") (pintype "passive"))
    )
    (net (code "363") (name "/M2") (class "Default")
      (node (ref "R14") (pin "2") (pinfunction "2_2") (pintype "passive"))
    )
    (net (code "364") (name "/MOUSECLOCK") (class "Default")
      (node (ref "U1") (pin "A18") (pinfunction "IO_L3N_5_A18") (pintype "bidirectional"))
    )
    (net (code "365") (name "/MOUSEDATA") (class "Default")
      (node (ref "U1") (pin "B18") (pinfunction "IO_L3P_5_B18") (pintype "bidirectional"))
    )
    (net (code "366") (name "/NEXUS_TCK") (class "Default")
      (node (ref "U1") (pin "A12") (pinfunction "IO_L2P_GC_VRN_LC_3_A12") (pintype "bidirectional"))
    )
    (net (code "367") (name "/NEXUS_TDI") (class "Default")
      (node (ref "U1") (pin "U21") (pinfunction "IO_L29N_9_U21") (pintype "bidirectional"))
    )
    (net (code "368") (name "/NEXUS_TDO") (class "Default")
      (node (ref "U1") (pin "B24") (pinfunction "IO_L10P_5_B24") (pintype "bidirectional"))
    )
    (net (code "369") (name "/NEXUS_TMS") (class "Default")
      (node (ref "U1") (pin "T24") (pinfunction "IO_L24P_CC_LC_9_T24") (pintype "bidirectional"))
    )
    (net (code "371") (name "/ONE_WIRE_DB_PB") (class "Default")
      (node (ref "U1") (pin "AA8") (pinfunction "IO_L26P_8_AA8") (pintype "bidirectional"))
    )
    (net (code "375") (name "/PROG_B") (class "Default")
      (node (ref "R24") (pin "2") (pinfunction "2_2") (pintype "passive"))
    )
    (net (code "376") (name "/REF_CLK") (class "Default")
      (node (ref "U1") (pin "AE10") (pinfunction "IO_L6P_GC_LC_4_AE10") (pintype "bidirectional"))
    )
    (net (code "377") (name "/RS232_CTS") (class "Default")
      (node (ref "U1") (pin "B14") (pinfunction "IO_L1N_GC_CC_LC_3_B14") (pintype "bidirectional"))
    )
    (net (code "378") (name "/RS232_RTS") (class "Default")
      (node (ref "U1") (pin "B13") (pinfunction "IO_L4P_GC_LC_3_B13") (pintype "bidirectional"))
    )
    (net (code "379") (name "/RS232_RX") (class "Default")
      (node (ref "U1") (pin "A16") (pinfunction "IO_L5P_GC_LC_3_A16") (pintype "bidirectional"))
    )
    (net (code "380") (name "/RS232_TX") (class "Default")
      (node (ref "U1") (pin "A15") (pinfunction "IO_L5N_GC_LC_3_A15") (pintype "bidirectional"))
    )
    (net (code "381") (name "/SCL") (class "Default")
      (node (ref "U1") (pin "AA7") (pinfunction "IO_L20P_8_AA7") (pintype "bidirectional"))
    )
    (net (code "382") (name "/SDA") (class "Default")
      (node (ref "U1") (pin "AA3") (pinfunction "IO_L7N_8_AA3") (pintype "bidirectional"))
    )
    (net (code "384") (name "/SPI_CLK") (class "Default")
      (node (ref "U1") (pin "D12") (pinfunction "IO_L8N_D16_CC_LC_1_D12") (pintype "bidirectional"))
    )
    (net (code "385") (name "/SPI_DIN") (class "Default")
      (node (ref "U1") (pin "C11") (pinfunction "IO_L6P_D21_LC_1_C11") (pintype "bidirectional"))
    )
    (net (code "386") (name "/SPI_DOUT") (class "Default")
      (node (ref "U1") (pin "G10") (pinfunction "IO_L9P_CC_LC_6_G10") (pintype "bidirectional"))
    )
    (net (code "387") (name "/SPI_MODE") (class "Default")
      (node (ref "U1") (pin "E14") (pinfunction "IO_L5N_D22_LC_1_E14") (pintype "bidirectional"))
    )
    (net (code "388") (name "/SPI_SEL") (class "Default")
      (node (ref "U1") (pin "E13") (pinfunction "IO_L8P_D17_CC_LC_1_E13") (pintype "bidirectional"))
    )
    (net (code "389") (name "/SRAM1_A0") (class "Default")
      (node (ref "U1") (pin "V22") (pinfunction "IO_L1N_7_V22") (pintype "bidirectional"))
    )
    (net (code "390") (name "/SRAM1_A1") (class "Default")
      (node (ref "U1") (pin "U22") (pinfunction "IO_L29P_9_U22") (pintype "bidirectional"))
    )
    (net (code "391") (name "/SRAM1_A2") (class "Default")
      (node (ref "U1") (pin "P23") (pinfunction "IO_L19P_9_P23") (pintype "bidirectional"))
    )
    (net (code "392") (name "/SRAM1_A3") (class "Default")
      (node (ref "U1") (pin "Y17") (pinfunction "IO_L27P_SM5_7_Y17") (pintype "bidirectional"))
    )
    (net (code "393") (name "/SRAM1_A4") (class "Default")
      (node (ref "U1") (pin "Y18") (pinfunction "IO_L21N_7_Y18") (pintype "bidirectional"))
    )
    (net (code "394") (name "/SRAM1_A5") (class "Default")
      (node (ref "U1") (pin "V20") (pinfunction "IO_L5N_7_V20") (pintype "bidirectional"))
    )
    (net (code "395") (name "/SRAM1_A6") (class "Default")
      (node (ref "U1") (pin "U20") (pinfunction "IO_L31P_9_U20") (pintype "bidirectional"))
    )
    (net (code "396") (name "/SRAM1_A7") (class "Default")
      (node (ref "U1") (pin "T20") (pinfunction "IO_L30N_9_T20") (pintype "bidirectional"))
    )
    (net (code "397") (name "/SRAM1_A8") (class "Default")
      (node (ref "U1") (pin "R20") (pinfunction "IO_L25P_CC_LC_9_R20") (pintype "bidirectional"))
    )
    (net (code "398") (name "/SRAM1_A9") (class "Default")
      (node (ref "U1") (pin "P20") (pinfunction "IO_L21P_9_P20") (pintype "bidirectional"))
    )
    (net (code "399") (name "/SRAM1_A10") (class "Default")
      (node (ref "U1") (pin "V21") (pinfunction "IO_L1P_7_V21") (pintype "bidirectional"))
    )
    (net (code "400") (name "/SRAM1_A11") (class "Default")
      (node (ref "U1") (pin "W21") (pinfunction "IO_L3P_7_W21") (pintype "bidirectional"))
    )
    (net (code "401") (name "/SRAM1_A12") (class "Default")
      (node (ref "U1") (pin "Y21") (pinfunction "IO_L20N_VREF_7_Y21") (pintype "bidirectional"))
    )
    (net (code "402") (name "/SRAM1_A13") (class "Default")
      (node (ref "U1") (pin "AA20") (pinfunction "IO_L26N_SM6_7_AA20") (pintype "bidirectional"))
    )
    (net (code "403") (name "/SRAM1_A14") (class "Default")
      (node (ref "U1") (pin "AA19") (pinfunction "IO_L26P_SM6_7_AA19") (pintype "bidirectional"))
    )
    (net (code "404") (name "/SRAM1_A15") (class "Default")
      (node (ref "U1") (pin "AC21") (pinfunction "IO_L24P_CC_LC_7_AC21") (pintype "bidirectional"))
    )
    (net (code "405") (name "/SRAM1_A16") (class "Default")
      (node (ref "U1") (pin "AD21") (pinfunction "IO_L32N_SM1_7_AD21") (pintype "bidirectional"))
    )
    (net (code "406") (name "/SRAM1_A17") (class "Default")
      (node (ref "U1") (pin "AC20") (pinfunction "IO_L28N_VREF_7_AC20") (pintype "bidirectional"))
    )
    (net (code "407") (name "/SRAM1_A18") (class "Default")
      (node (ref "U1") (pin "AA18") (pinfunction "IO_L21P_7_AA18") (pintype "bidirectional"))
    )
    (net (code "408") (name "/SRAM1_D0") (class "Default")
      (node (ref "U1") (pin "Y20") (pinfunction "IO_L20P_7_Y20") (pintype "bidirectional"))
    )
    (net (code "409") (name "/SRAM1_D1") (class "Default")
      (node (ref "U1") (pin "AD11") (pinfunction "IO_L8N_GC_CC_LC_4_AD11") (pintype "bidirectional"))
    )
    (net (code "410") (name "/SRAM1_D2") (class "Default")
      (node (ref "U1") (pin "T19") (pinfunction "IO_L31N_9_T19") (pintype "bidirectional"))
    )
    (net (code "411") (name "/SRAM1_D3") (class "Default")
      (node (ref "U1") (pin "R19") (pinfunction "IO_L25N_CC_LC_9_R19") (pintype "bidirectional"))
    )
    (net (code "412") (name "/SRAM1_D4") (class "Default")
      (node (ref "U1") (pin "P22") (pinfunction "IO_L19N_9_P22") (pintype "bidirectional"))
    )
    (net (code "413") (name "/SRAM1_D5") (class "Default")
      (node (ref "U1") (pin "P19") (pinfunction "IO_L21N_9_P19") (pintype "bidirectional"))
    )
    (net (code "414") (name "/SRAM1_D6") (class "Default")
      (node (ref "U1") (pin "N19") (pinfunction "IO_L9N_CC_LC_9_N19") (pintype "bidirectional"))
    )
    (net (code "415") (name "/SRAM1_D7") (class "Default")
      (node (ref "U1") (pin "N22") (pinfunction "IO_L16N_9_N22") (pintype "bidirectional"))
    )
    (net (code "416") (name "/SRAM1_D8") (class "Default")
      (node (ref "U1") (pin "AA17") (pinfunction "IO_L27N_SM5_7_AA17") (pintype "bidirectional"))
    )
    (net (code "417") (name "/SRAM1_D9") (class "Default")
      (node (ref "U1") (pin "AA16") (pinfunction "IO_L3P_D11_LC_2_AA16") (pintype "bidirectional"))
    )
    (net (code "418") (name "/SRAM1_D10") (class "Default")
      (node (ref "U1") (pin "AA15") (pinfunction "IO_L3N_D10_LC_2_AA15") (pintype "bidirectional"))
    )
    (net (code "419") (name "/SRAM1_D11") (class "Default")
      (node (ref "U1") (pin "Y23") (pinfunction "IO_L12N_VREF_7_Y23") (pintype "bidirectional"))
    )
    (net (code "420") (name "/SRAM1_D12") (class "Default")
      (node (ref "U1") (pin "AA24") (pinfunction "IO_L8P_CC_LC_7_AA24") (pintype "bidirectional"))
    )
    (net (code "421") (name "/SRAM1_D13") (class "Default")
      (node (ref "U1") (pin "AA23") (pinfunction "IO_L14N_7_AA23") (pintype "bidirectional"))
    )
    (net (code "422") (name "/SRAM1_D14") (class "Default")
      (node (ref "U1") (pin "AB24") (pinfunction "IO_L7P_7_AB24") (pintype "bidirectional"))
    )
    (net (code "423") (name "/SRAM1_D15") (class "Default")
      (node (ref "U1") (pin "AC16") (pinfunction "IO_L7P_D3_LC_2_AC16") (pintype "bidirectional"))
    )
    (net (code "425") (name "/SRAM1_NBHE") (class "Default")
      (node (ref "U1") (pin "AD19") (pinfunction "IO_L25P_CC_SM7_LC_7_AD19") (pintype "bidirectional"))
    )
    (net (code "426") (name "/SRAM1_NBLE") (class "Default")
      (node (ref "U1") (pin "AC18") (pinfunction "IO_L29P_SM4_7_AC18") (pintype "bidirectional"))
    )
    (net (code "427") (name "/SRAM1_NCS") (class "Default")
      (node (ref "U1") (pin "Y19") (pinfunction "IO_L18P_7_Y19") (pintype "bidirectional"))
    )
    (net (code "428") (name "/SRAM1_NOE") (class "Default")
      (node (ref "U1") (pin "AC19") (pinfunction "IO_L25N_CC_SM7_LC_7_AC19") (pintype "bidirectional"))
    )
    (net (code "429") (name "/SRAM1_NWE") (class "Default")
      (node (ref "U1") (pin "W20") (pinfunction "IO_L5P_7_W20") (pintype "bidirectional"))
    )
    (net (code "431") (name "/SRAM2_A0") (class "Default")
      (node (ref "U1") (pin "N25") (pinfunction "IO_L15P_9_N25") (pintype "bidirectional"))
    )
    (net (code "432") (name "/SRAM2_A1") (class "Default")
      (node (ref "U1") (pin "M26") (pinfunction "IO_L12N_VREF_9_M26") (pintype "bidirectional"))
    )
    (net (code "433") (name "/SRAM2_A2") (class "Default")
      (node (ref "U1") (pin "M25") (pinfunction "IO_L11P_9_M25") (pintype "bidirectional"))
    )
    (net (code "434") (name "/SRAM2_A3") (class "Default")
      (node (ref "U1") (pin "L26") (pinfunction "IO_L12P_9_L26") (pintype "bidirectional"))
    )
    (net (code "435") (name "/SRAM2_A4") (class "Default")
      (node (ref "U1") (pin "AD22") (pinfunction "IO_L15P_7_AD22") (pintype "bidirectional"))
    )
    (net (code "436") (name "/SRAM2_A5") (class "Default")
      (node (ref "U1") (pin "U23") (pinfunction "IO_L27P_9_U23") (pintype "bidirectional"))
    )
    (net (code "437") (name "/SRAM2_A6") (class "Default")
      (node (ref "U1") (pin "T23") (pinfunction "IO_L24N_CC_LC_9_T23") (pintype "bidirectional"))
    )
    (net (code "438") (name "/SRAM2_A7") (class "Default")
      (node (ref "U1") (pin "R24") (pinfunction "IO_L22P_9_R24") (pintype "bidirectional"))
    )
    (net (code "439") (name "/SRAM2_A8") (class "Default")
      (node (ref "U1") (pin "R23") (pinfunction "IO_L22N_9_R23") (pintype "bidirectional"))
    )
    (net (code "440") (name "/SRAM2_A9") (class "Default")
      (node (ref "U1") (pin "P24") (pinfunction "IO_L18N_9_P24") (pintype "bidirectional"))
    )
    (net (code "441") (name "/SRAM2_A10") (class "Default")
      (node (ref "U1") (pin "P25") (pinfunction "IO_L18P_9_P25") (pintype "bidirectional"))
    )
    (net (code "442") (name "/SRAM2_A11") (class "Default")
      (node (ref "U1") (pin "R26") (pinfunction "IO_L20P_9_R26") (pintype "bidirectional"))
    )
    (net (code "443") (name "/SRAM2_A12") (class "Default")
      (node (ref "U1") (pin "R25") (pinfunction "IO_L20N_VREF_9_R25") (pintype "bidirectional"))
    )
    (net (code "444") (name "/SRAM2_A13") (class "Default")
      (node (ref "U1") (pin "T26") (pinfunction "IO_L26P_9_T26") (pintype "bidirectional"))
    )
    (net (code "445") (name "/SRAM2_A14") (class "Default")
      (node (ref "U1") (pin "U26") (pinfunction "IO_L26N_9_U26") (pintype "bidirectional"))
    )
    (net (code "446") (name "/SRAM2_A15") (class "Default")
      (node (ref "U1") (pin "AD26") (pinfunction "IO_L11N_7_AD26") (pintype "bidirectional"))
    )
    (net (code "447") (name "/SRAM2_A16") (class "Default")
      (node (ref "U1") (pin "AE24") (pinfunction "IO_L22N_7_AE24") (pintype "bidirectional"))
    )
    (net (code "448") (name "/SRAM2_A17") (class "Default")
      (node (ref "U1") (pin "AF24") (pinfunction "IO_L22P_7_AF24") (pintype "bidirectional"))
    )
    (net (code "449") (name "/SRAM2_A18") (class "Default")
      (node (ref "U1") (pin "U25") (pinfunction "IO_L28P_9_U25") (pintype "bidirectional"))
    )
    (net (code "450") (name "/SRAM2_D0") (class "Default")
      (node (ref "U1") (pin "AD23") (pinfunction "IO_L15N_7_AD23") (pintype "bidirectional"))
    )
    (net (code "451") (name "/SRAM2_D1") (class "Default")
      (node (ref "U1") (pin "AC23") (pinfunction "IO_L16P_7_AC23") (pintype "bidirectional"))
    )
    (net (code "452") (name "/SRAM2_D2") (class "Default")
      (node (ref "U1") (pin "AC24") (pinfunction "IO_L16N_7_AC24") (pintype "bidirectional"))
    )
    (net (code "453") (name "/SRAM2_D3") (class "Default")
      (node (ref "U1") (pin "AB23") (pinfunction "IO_L14P_7_AB23") (pintype "bidirectional"))
    )
    (net (code "454") (name "/SRAM2_D4") (class "Default")
      (node (ref "U1") (pin "Y24") (pinfunction "IO_L8N_CC_LC_7_Y24") (pintype "bidirectional"))
    )
    (net (code "455") (name "/SRAM2_D5") (class "Default")
      (node (ref "U1") (pin "W23") (pinfunction "IO_L4P_7_W23") (pintype "bidirectional"))
    )
    (net (code "456") (name "/SRAM2_D6") (class "Default")
      (node (ref "U1") (pin "W24") (pinfunction "IO_L4N_VREF_7_W24") (pintype "bidirectional"))
    )
    (net (code "457") (name "/SRAM2_D7") (class "Default")
      (node (ref "U1") (pin "V23") (pinfunction "IO_L27N_9_V23") (pintype "bidirectional"))
    )
    (net (code "458") (name "/SRAM2_D8") (class "Default")
      (node (ref "U1") (pin "V26") (pinfunction "IO_L32P_9_V26") (pintype "bidirectional"))
    )
    (net (code "459") (name "/SRAM2_D9") (class "Default")
      (node (ref "U1") (pin "V25") (pinfunction "IO_L32N_9_V25") (pintype "bidirectional"))
    )
    (net (code "460") (name "/SRAM2_D10") (class "Default")
      (node (ref "U1") (pin "W26") (pinfunction "IO_L2N_7_W26") (pintype "bidirectional"))
    )
    (net (code "461") (name "/SRAM2_D11") (class "Default")
      (node (ref "U1") (pin "W25") (pinfunction "IO_L2P_7_W25") (pintype "bidirectional"))
    )
    (net (code "462") (name "/SRAM2_D12") (class "Default")
      (node (ref "U1") (pin "Y26") (pinfunction "IO_L6N_7_Y26") (pintype "bidirectional"))
    )
    (net (code "463") (name "/SRAM2_D13") (class "Default")
      (node (ref "U1") (pin "Y25") (pinfunction "IO_L6P_7_Y25") (pintype "bidirectional"))
    )
    (net (code "464") (name "/SRAM2_D14") (class "Default")
      (node (ref "U1") (pin "AA26") (pinfunction "IO_L10N_7_AA26") (pintype "bidirectional"))
    )
    (net (code "465") (name "/SRAM2_D15") (class "Default")
      (node (ref "U1") (pin "AB26") (pinfunction "IO_L10P_7_AB26") (pintype "bidirectional"))
    )
    (net (code "467") (name "/SRAM2_NBHE") (class "Default")
      (node (ref "U1") (pin "AC26") (pinfunction "IO_L9N_CC_LC_7_AC26") (pintype "bidirectional"))
    )
    (net (code "468") (name "/SRAM2_NBLE") (class "Default")
      (node (ref "U1") (pin "AB25") (pinfunction "IO_L7N_7_AB25") (pintype "bidirectional"))
    )
    (net (code "469") (name "/SRAM2_NCS") (class "Default")
      (node (ref "U1") (pin "AC22") (pinfunction "IO_L13P_7_AC22") (pintype "bidirectional"))
    )
    (net (code "470") (name "/SRAM2_NOE") (class "Default")
      (node (ref "U1") (pin "AC25") (pinfunction "IO_L9P_CC_LC_7_AC25") (pintype "bidirectional"))
    )
    (net (code "471") (name "/SRAM2_NWE") (class "Default")
      (node (ref "U1") (pin "U24") (pinfunction "IO_L28N_VREF_9_U24") (pintype "bidirectional"))
    )
    (net (code "473") (name "/STATUS_LED") (class "Default")
      (node (ref "NT6") (pin "1") (pinfunction "Net1_1") (pintype "passive"))
    )
    (net (code "474") (name "/SW0") (class "Default")
      (node (ref "U1") (pin "AE18") (pinfunction "IO_L31N_SM2_7_AE18") (pintype "bidirectional"))
    )
    (net (code "475") (name "/SW1") (class "Default")
      (node (ref "U1") (pin "AF19") (pinfunction "IO_L17P_7_AF19") (pintype "bidirectional"))
    )
    (net (code "476") (name "/SW2") (class "Default")
      (node (ref "U1") (pin "AF20") (pinfunction "IO_L17N_7_AF20") (pintype "bidirectional"))
    )
    (net (code "477") (name "/SW3") (class "Default")
      (node (ref "U1") (pin "AF21") (pinfunction "IO_L30P_SM3_7_AF21") (pintype "bidirectional"))
    )
    (net (code "478") (name "/SW4") (class "Default")
      (node (ref "U1") (pin "AE21") (pinfunction "IO_L32P_SM1_7_AE21") (pintype "bidirectional"))
    )
    (net (code "480") (name "/TCK") (class "Default")
      (node (ref "R9") (pin "2") (pinfunction "2_2") (pintype "passive"))
    )
    (net (code "481") (name "/TDI") (class "Default")
      (node (ref "R12") (pin "2") (pinfunction "2_2") (pintype "passive"))
    )
    (net (code "482") (name "/TDO") (class "Default")
      (node (ref "R10") (pin "2") (pinfunction "2_2") (pintype "passive"))
    )
    (net (code "484") (name "/TMS") (class "Default")
      (node (ref "R8") (pin "2") (pinfunction "2_2") (pintype "passive"))
    )
    (net (code "485") (name "/UNUSED1") (class "Default")
      (node (ref "U1") (pin "D23") (pinfunction "IO_L21P_5_D23") (pintype "bidirectional"))
    )
    (net (code "486") (name "/UNUSED2") (class "Default")
      (node (ref "U1") (pin "AB22") (pinfunction "IO_L13N_7_AB22") (pintype "bidirectional"))
    )
    (net (code "487") (name "/UNUSED3") (class "Default")
      (node (ref "U1") (pin "Y22") (pinfunction "IO_L12P_7_Y22") (pintype "bidirectional"))
    )
    (net (code "488") (name "/UNUSED4") (class "Default")
      (node (ref "U1") (pin "M8") (pinfunction "IO_L9P_CC_LC_10_M8") (pintype "bidirectional"))
    )
    (net (code "489") (name "/UNUSED5") (class "Default")
      (node (ref "U1") (pin "L8") (pinfunction "IO_L9N_CC_LC_10_L8") (pintype "bidirectional"))
    )
    (net (code "490") (name "/UNUSED6") (class "Default")
      (node (ref "U1") (pin "W22") (pinfunction "IO_L3N_7_W22") (pintype "bidirectional"))
    )
    (net (code "493") (name "/VRN_7") (class "Default")
      (node (ref "U1") (pin "AD17") (pinfunction "IO_L7P_GC_VRN_LC_4_AD17") (pintype "bidirectional"))
    )
    (net (code "494") (name "/VRP_7") (class "Default")
      (node (ref "U1") (pin "AD16") (pinfunction "IO_L7N_GC_VRP_LC_4_AD16") (pintype "bidirectional"))
    )
    (net (code "514") (name "3V3") (class "Default")
      (node (ref "C23_CM") (pin "1") (pinfunction "1_1") (pintype "passive"))
      (node (ref "C24_CM") (pin "1") (pinfunction "1_1") (pintype "passive"))
      (node (ref "R1") (pin "2") (pinfunction "2_2") (pintype "passive"))
      (node (ref "R2") (pin "2") (pinfunction "2_2") (pintype "passive"))
      (node (ref "R3") (pin "2") (pinfunction "2_2") (pintype "passive"))
      (node (ref "R4") (pin "2") (pinfunction "2_2") (pintype "passive"))
    )
    (net (code "515") (name "GND") (class "Default")
      (node (ref "C23_CM") (pin "2") (pinfunction "2_2") (pintype "passive"))
      (node (ref "C24_CM") (pin "2") (pinfunction "2_2") (pintype "passive"))
      (node (ref "NT2") (pin "2") (pinfunction "Net2_2") (pintype "passive"))
      (node (ref "NT3") (pin "2") (pinfunction "Net2_2") (pintype "passive"))
      (node (ref "NT4") (pin "2") (pinfunction "Net2_2") (pintype "passive"))
      (node (ref "NT5") (pin "2") (pinfunction "Net2_2") (pintype "passive"))
    )
    (net (code "516") (name "unconnected-(U1C-IO_L2N_GC_VRP_LC_3-PadA11)") (class "Default")
      (node (ref "U1") (pin "A11") (pinfunction "IO_L2N_GC_VRP_LC_3_A11") (pintype "bidirectional"))
    )
    (net (code "517") (name "unconnected-(U1E-IO_L23N_VRP_5-PadG21)") (class "Default")
      (node (ref "U1") (pin "G21") (pinfunction "IO_L23N_VRP_5_G21") (pintype "bidirectional"))
    )
    (net (code "518") (name "unconnected-(U1E-IO_L23P_VRN_5-PadG22)") (class "Default")
      (node (ref "U1") (pin "G22") (pinfunction "IO_L23P_VRN_5_G22") (pintype "bidirectional"))
    )
    (net (code "519") (name "unconnected-(U1F-IO_L6N_6-PadA5)") (class "Default")
      (node (ref "U1") (pin "A5") (pinfunction "IO_L6N_6_A5") (pintype "bidirectional"))
    )
    (net (code "520") (name "unconnected-(U1F-IO_L7P_6-PadE9)") (class "Default")
      (node (ref "U1") (pin "E9") (pinfunction "IO_L7P_6_E9") (pintype "bidirectional"))
    )
    (net (code "521") (name "unconnected-(U1F-IO_L12N_VREF_6-PadD5)") (class "Default")
      (node (ref "U1") (pin "D5") (pinfunction "IO_L12N_VREF_6_D5") (pintype "bidirectional"))
    )
    (net (code "522") (name "unconnected-(U1F-IO_L12P_6-PadC5)") (class "Default")
      (node (ref "U1") (pin "C5") (pinfunction "IO_L12P_6_C5") (pintype "bidirectional"))
    )
    (net (code "523") (name "unconnected-(U1F-IO_L14N_6-PadB3)") (class "Default")
      (node (ref "U1") (pin "B3") (pinfunction "IO_L14N_6_B3") (pintype "bidirectional"))
    )
    (net (code "524") (name "unconnected-(U1F-IO_L14P_6-PadA3)") (class "Default")
      (node (ref "U1") (pin "A3") (pinfunction "IO_L14P_6_A3") (pintype "bidirectional"))
    )
    (net (code "525") (name "unconnected-(U1F-IO_L15N_6-PadB4)") (class "Default")
      (node (ref "U1") (pin "B4") (pinfunction "IO_L15N_6_B4") (pintype "bidirectional"))
    )
    (net (code "526") (name "unconnected-(U1F-IO_L15P_6-PadA4)") (class "Default")
      (node (ref "U1") (pin "A4") (pinfunction "IO_L15P_6_A4") (pintype "bidirectional"))
    )
    (net (code "527") (name "unconnected-(U1F-IO_L17P_6-PadE7)") (class "Default")
      (node (ref "U1") (pin "E7") (pinfunction "IO_L17P_6_E7") (pintype "bidirectional"))
    )
    (net (code "528") (name "unconnected-(U1F-IO_L21N_6-PadH7)") (class "Default")
      (node (ref "U1") (pin "H7") (pinfunction "IO_L21N_6_H7") (pintype "bidirectional"))
    )
    (net (code "529") (name "unconnected-(U1F-IO_L21P_6-PadH8)") (class "Default")
      (node (ref "U1") (pin "H8") (pinfunction "IO_L21P_6_H8") (pintype "bidirectional"))
    )
    (net (code "530") (name "unconnected-(U1F-IO_L23N_VRP_6-PadG5)") (class "Default")
      (node (ref "U1") (pin "G5") (pinfunction "IO_L23N_VRP_6_G5") (pintype "bidirectional"))
    )
    (net (code "531") (name "unconnected-(U1F-IO_L23P_VRN_6-PadG6)") (class "Default")
      (node (ref "U1") (pin "G6") (pinfunction "IO_L23P_VRN_6_G6") (pintype "bidirectional"))
    )
    (net (code "532") (name "unconnected-(U1G-IO_L11P_7-PadAD25)") (class "Default")
      (node (ref "U1") (pin "AD25") (pinfunction "IO_L11P_7_AD25") (pintype "bidirectional"))
    )
    (net (code "533") (name "unconnected-(U1G-IO_L23N_VRP_7-PadAD20)") (class "Default")
      (node (ref "U1") (pin "AD20") (pinfunction "IO_L23N_VRP_7_AD20") (pintype "bidirectional"))
    )
    (net (code "534") (name "unconnected-(U1G-IO_L23P_VRN_7-PadAE20)") (class "Default")
      (node (ref "U1") (pin "AE20") (pinfunction "IO_L23P_VRN_7_AE20") (pintype "bidirectional"))
    )
    (net (code "535") (name "unconnected-(U1H-IO_L23N_VRP_8-PadAD7)") (class "Default")
      (node (ref "U1") (pin "AD7") (pinfunction "IO_L23N_VRP_8_AD7") (pintype "bidirectional"))
    )
    (net (code "536") (name "unconnected-(U1H-IO_L23P_VRN_8-PadAE7)") (class "Default")
      (node (ref "U1") (pin "AE7") (pinfunction "IO_L23P_VRN_8_AE7") (pintype "bidirectional"))
    )
    (net (code "537") (name "unconnected-(U1I-IO_L15N_9-PadN24)") (class "Default")
      (node (ref "U1") (pin "N24") (pinfunction "IO_L15N_9_N24") (pintype "bidirectional"))
    )
    (net (code "538") (name "unconnected-(U1I-IO_L23N_VRP_9-PadR21)") (class "Default")
      (node (ref "U1") (pin "R21") (pinfunction "IO_L23N_VRP_9_R21") (pintype "bidirectional"))
    )
    (net (code "539") (name "unconnected-(U1I-IO_L23P_VRN_9-PadR22)") (class "Default")
      (node (ref "U1") (pin "R22") (pinfunction "IO_L23P_VRN_9_R22") (pintype "bidirectional"))
    )
    (net (code "540") (name "unconnected-(U1I-IO_L30P_9-PadT21)") (class "Default")
      (node (ref "U1") (pin "T21") (pinfunction "IO_L30P_9_T21") (pintype "bidirectional"))
    )
    (net (code "541") (name "unconnected-(U1J-IO_L23N_VRP_10-PadR5)") (class "Default")
      (node (ref "U1") (pin "R5") (pinfunction "IO_L23N_VRP_10_R5") (pintype "bidirectional"))
    )
    (net (code "542") (name "unconnected-(U1J-IO_L23P_VRN_10-PadR6)") (class "Default")
      (node (ref "U1") (pin "R6") (pinfunction "IO_L23P_VRN_10_R6") (pintype "bidirectional"))
    )
  )
)
